# 612_jetracer_esp32s3_030006.net
KiCad netlist of a schematic drawn in EAGLE
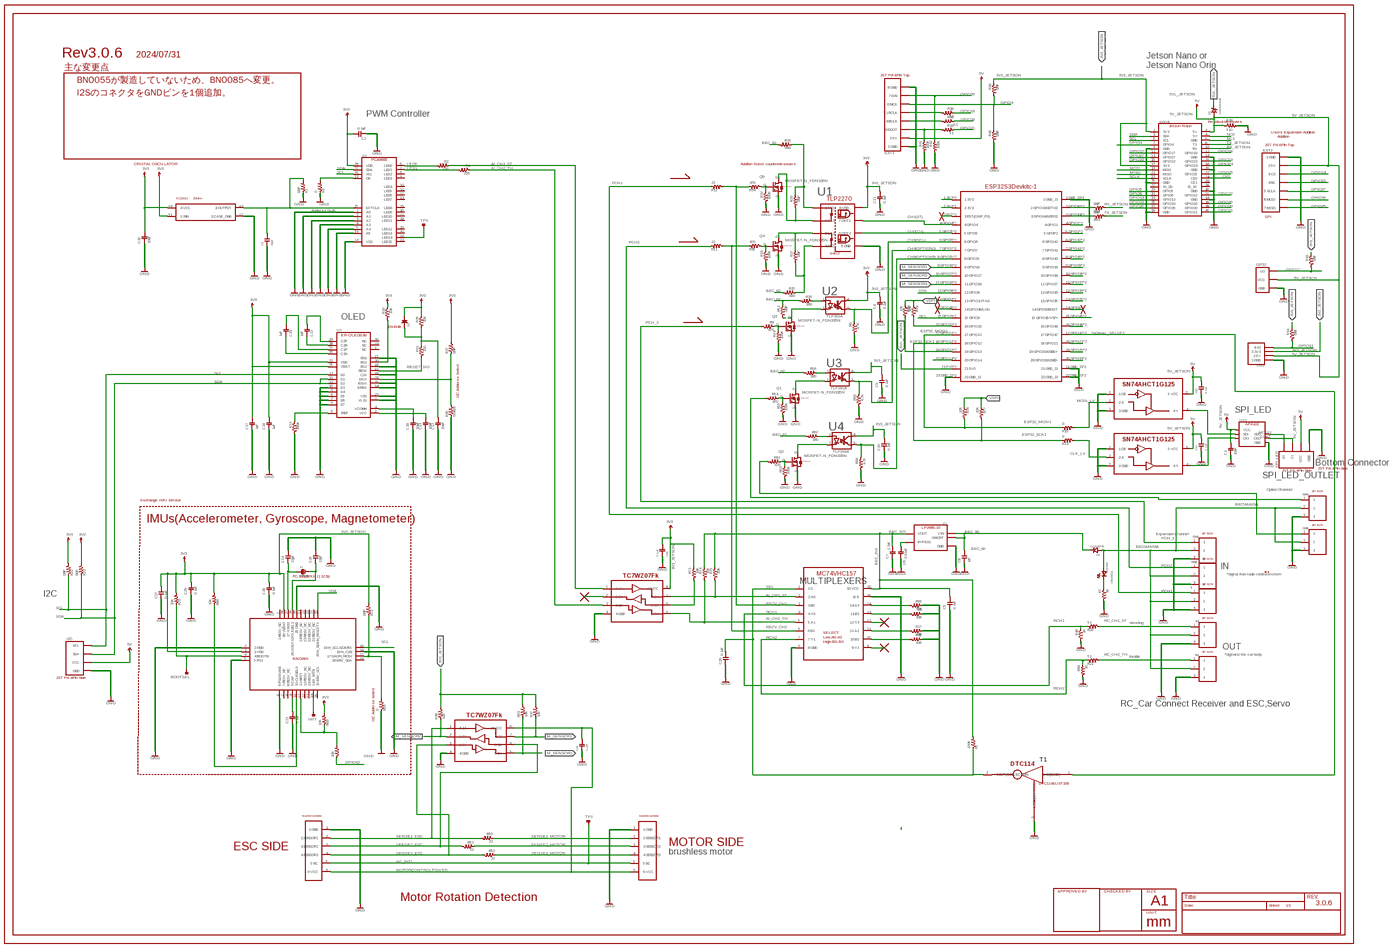
[diagram p0: schematic, sheet 1, overview]
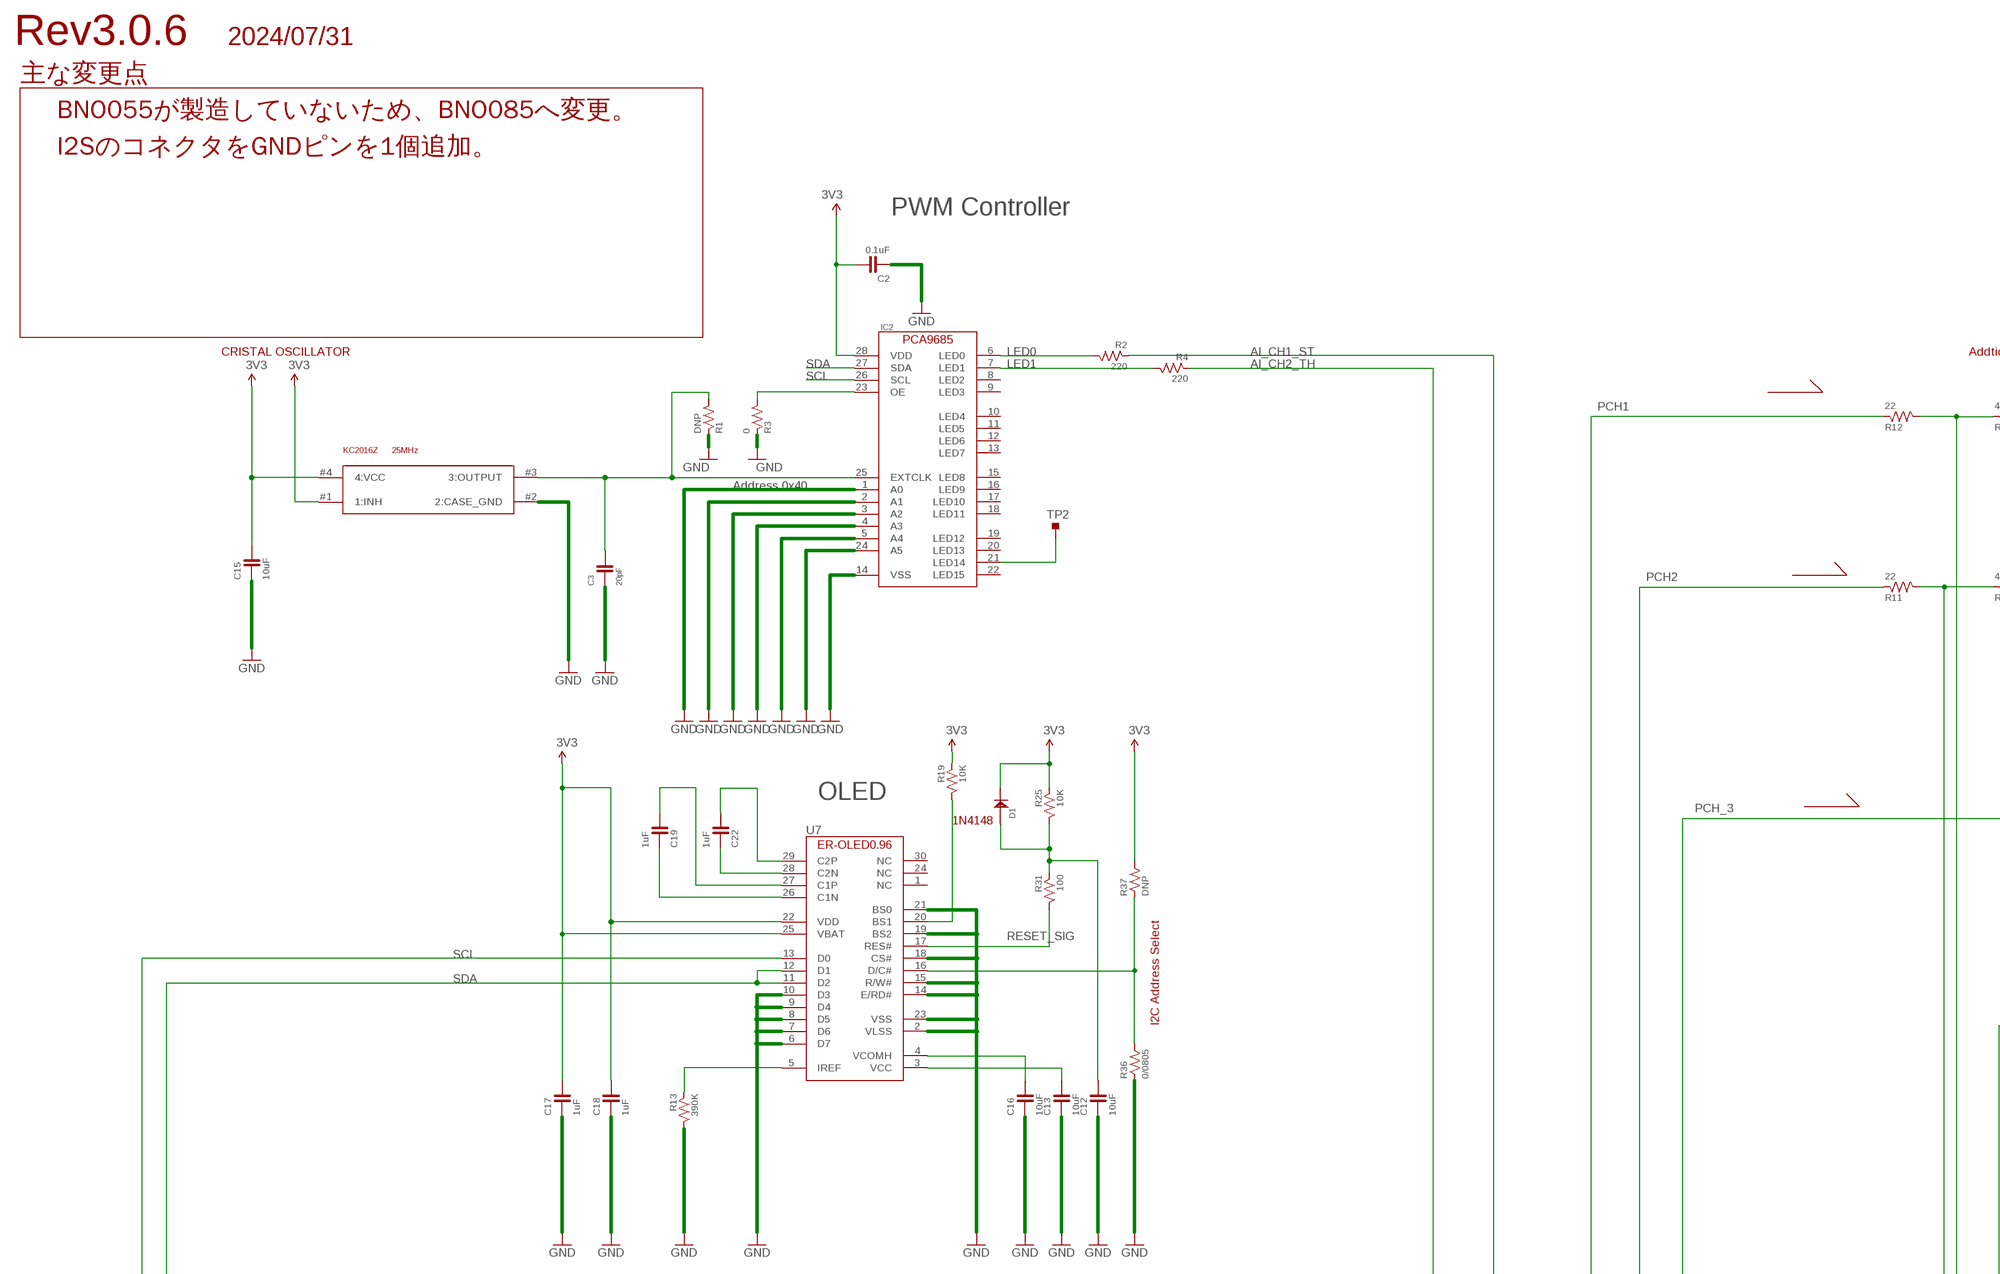
[diagram p1: schematic, sheet 1, part 1 of 4]
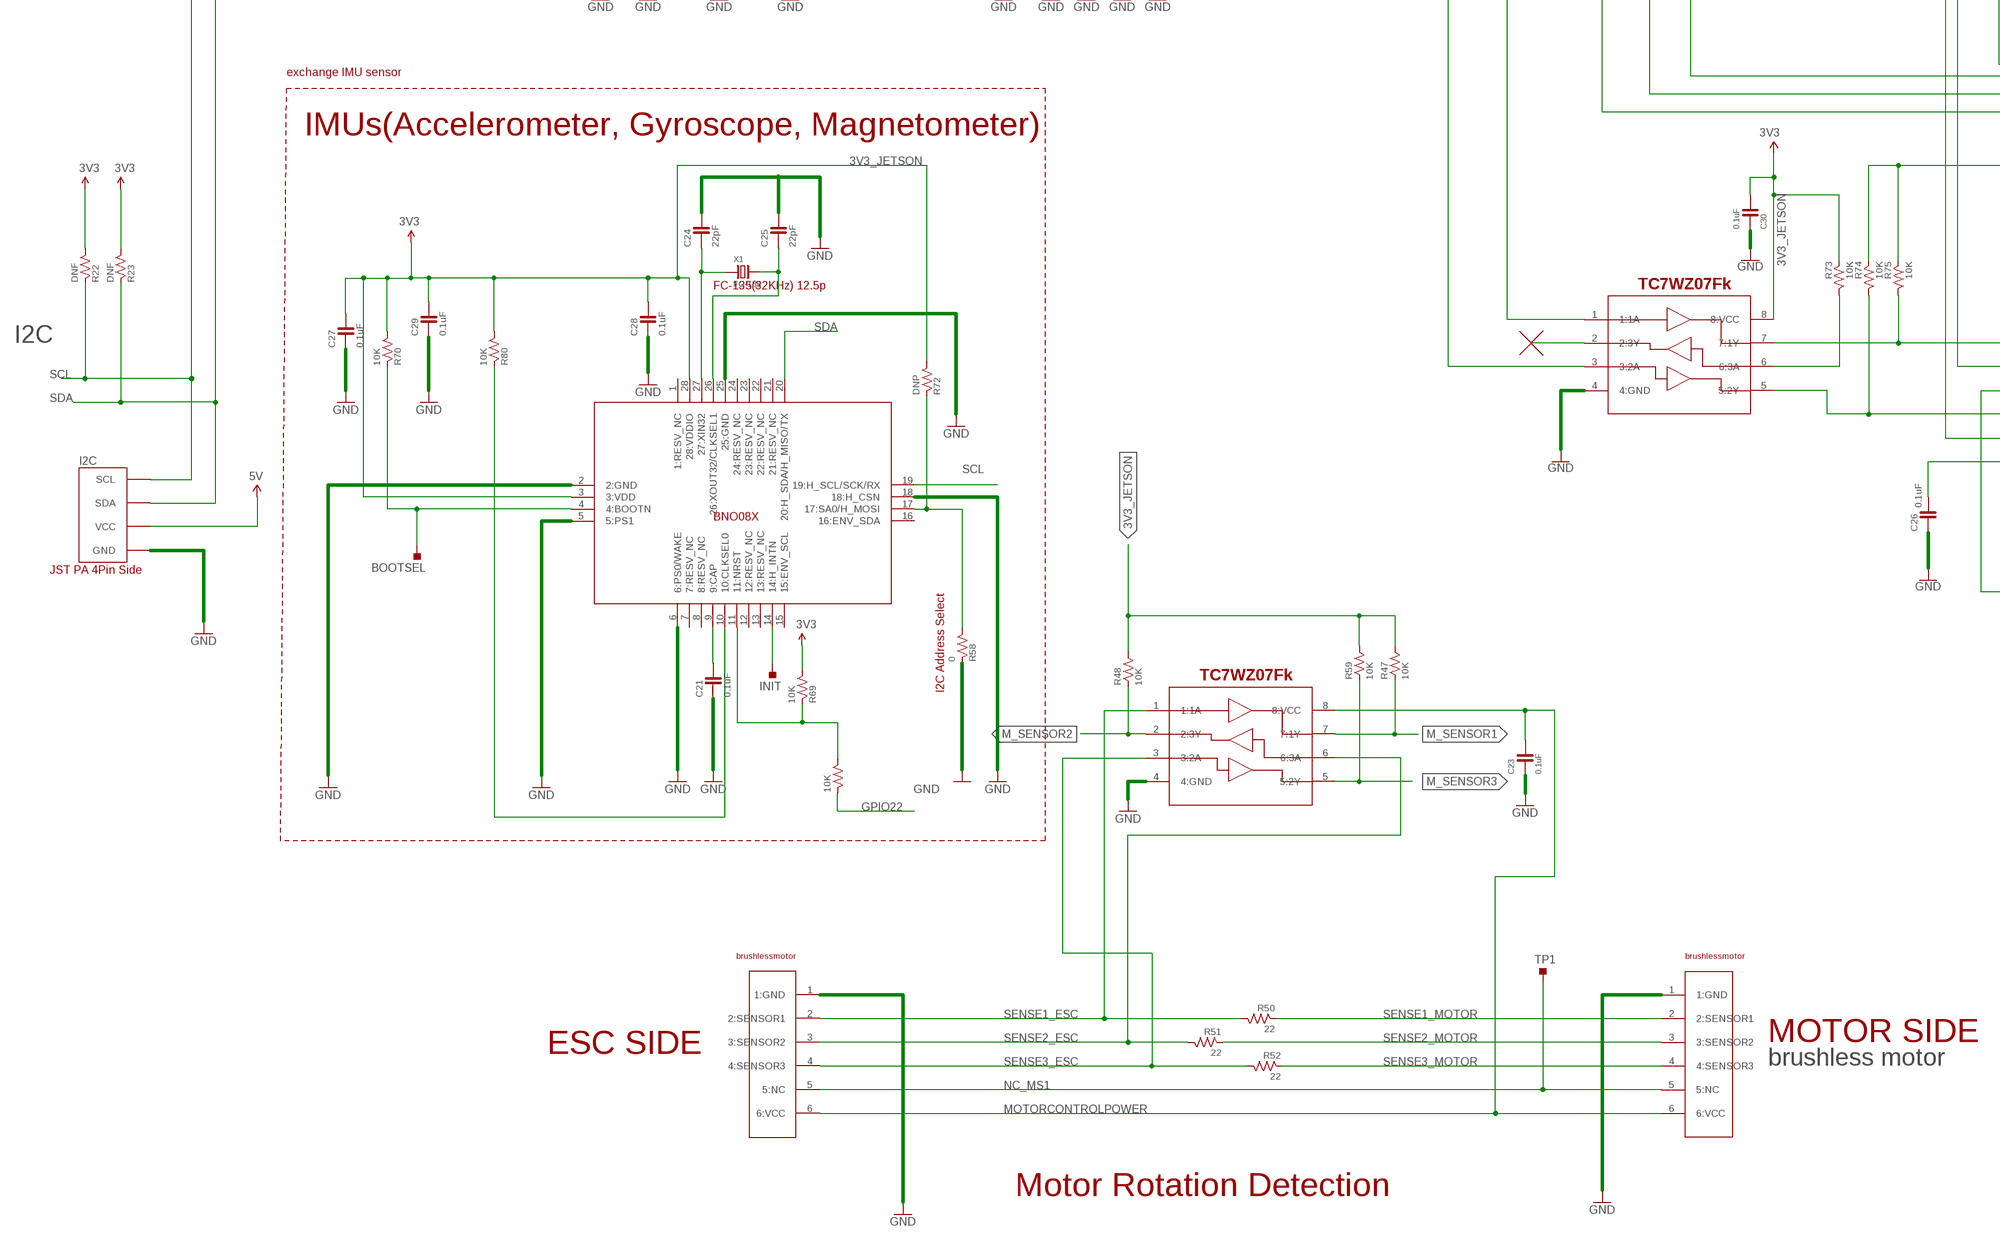
[diagram p2: schematic, sheet 1, part 2 of 4]
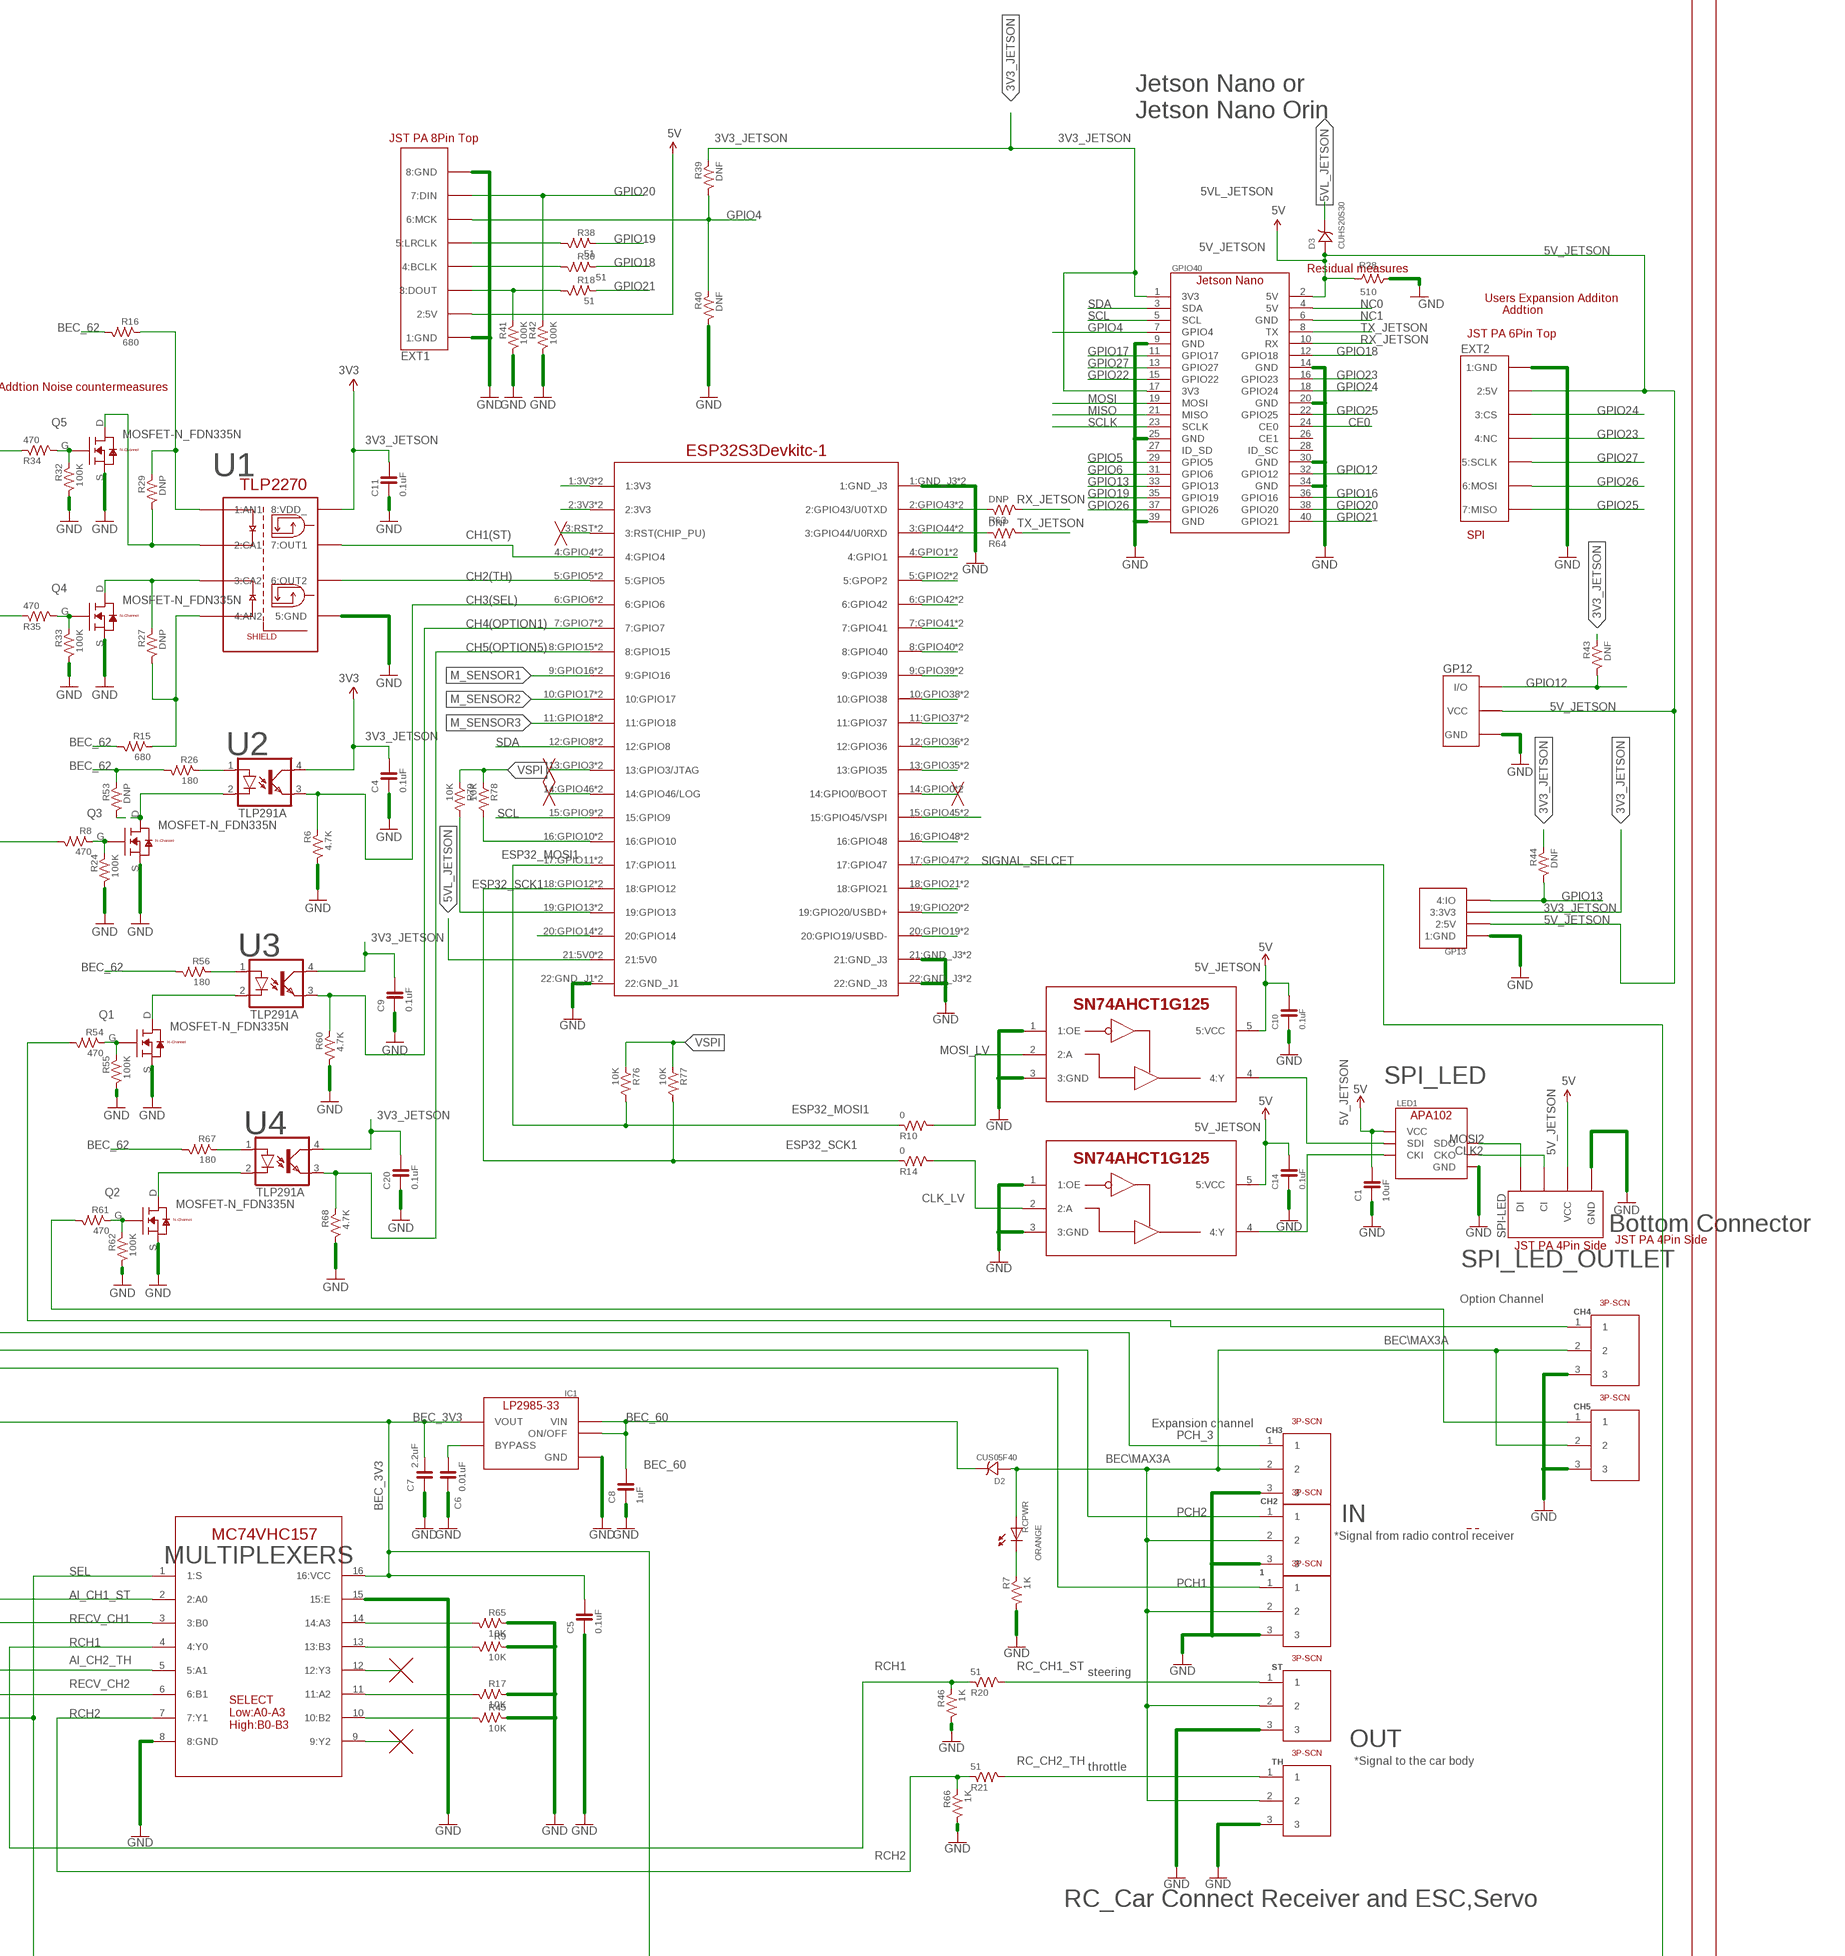
[diagram p3: schematic, sheet 1, part 3 of 4]
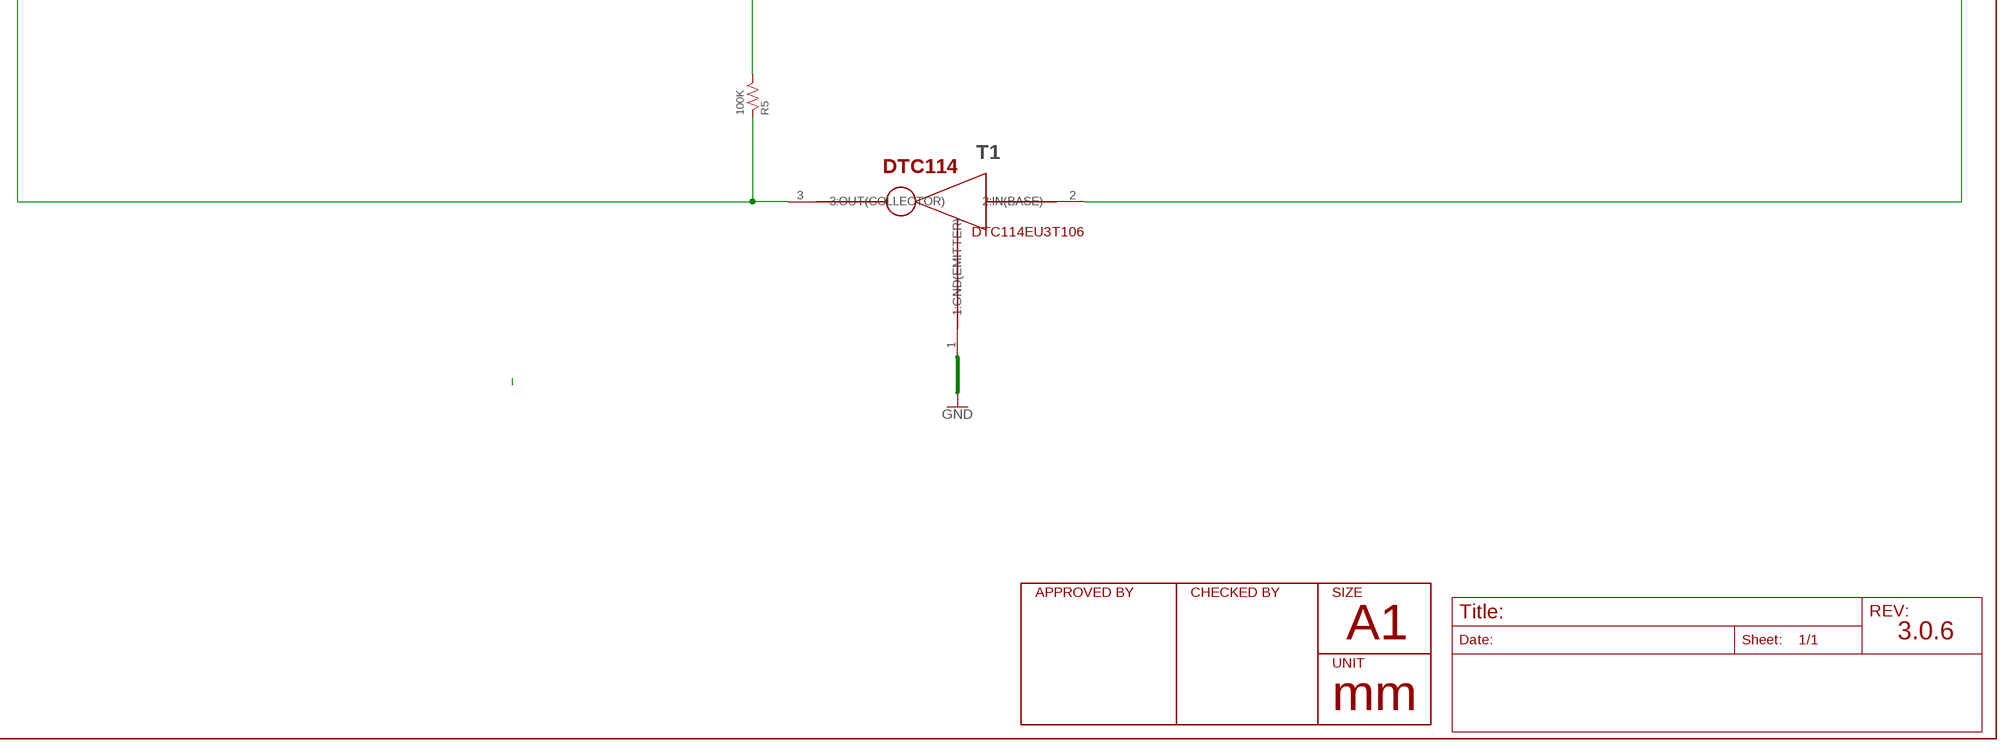
[diagram p4: schematic, sheet 1, part 4 of 4]

(export (version "E")
  (design (tool "Eeschema 10.0.6"))
  (components
    (comp (ref "1")
      (value "3P-SCN")
      (footprint "eagle-import:3P-SCN")
      (libsource (lib "eagle-import") (part "3P-SCN"))
    )
    (comp (ref "BOOTSEL")
      (value "TESTPOINT_TPS-SMD-10SN")
      (footprint "eagle-import:TESTPOINT_SMD-10SN")
      (libsource (lib "eagle-import") (part "TESTPOINT_TPS-SMD-10SN"))
    )
    (comp (ref "C1")
      (value "10uF")
      (footprint "eagle-import:0603")
      (libsource (lib "eagle-import") (part "CAPACITOR-0603"))
    )
    (comp (ref "C2")
      (value "0.1uF")
      (footprint "eagle-import:0603")
      (libsource (lib "eagle-import") (part "CAPACITOR-0603"))
    )
    (comp (ref "C3")
      (value "20pF")
      (footprint "eagle-import:0402")
      (libsource (lib "eagle-import") (part "CAPACITOR-0402"))
    )
    (comp (ref "C4")
      (value "0.1uF")
      (footprint "eagle-import:0603")
      (libsource (lib "eagle-import") (part "CAPACITOR-0603"))
    )
    (comp (ref "C5")
      (value "0.1uF")
      (footprint "eagle-import:0603")
      (fields (field (name "SPICEPREFIX") "C"))
      (libsource (lib "eagle-import") (part "CAPACITOR-0603"))
    )
    (comp (ref "C6")
      (value "0.01uF")
      (footprint "eagle-import:0603")
      (libsource (lib "eagle-import") (part "CAPACITOR-0603"))
    )
    (comp (ref "C7")
      (value "2.2uF")
      (footprint "eagle-import:0603")
      (libsource (lib "eagle-import") (part "CAPACITOR-0603"))
    )
    (comp (ref "C8")
      (value "1uF")
      (footprint "eagle-import:0603")
      (libsource (lib "eagle-import") (part "CAPACITOR-0603"))
    )
    (comp (ref "C9")
      (value "0.1uF")
      (footprint "eagle-import:0603")
      (libsource (lib "eagle-import") (part "CAPACITOR-0603"))
    )
    (comp (ref "C10")
      (value "0.1uF")
      (footprint "eagle-import:0402")
      (libsource (lib "eagle-import") (part "CAPACITOR-0402"))
    )
    (comp (ref "C11")
      (value "0.1uF")
      (footprint "eagle-import:0603")
      (libsource (lib "eagle-import") (part "CAPACITOR-0603"))
    )
    (comp (ref "C12")
      (value "10uF")
      (footprint "eagle-import:0603")
      (libsource (lib "eagle-import") (part "CAPACITOR-0603"))
    )
    (comp (ref "C13")
      (value "10uF")
      (footprint "eagle-import:0603")
      (libsource (lib "eagle-import") (part "CAPACITOR-0603"))
    )
    (comp (ref "C14")
      (value "0.1uF")
      (footprint "eagle-import:0402")
      (libsource (lib "eagle-import") (part "CAPACITOR-0402"))
    )
    (comp (ref "C15")
      (value "10uF")
      (footprint "eagle-import:0603")
      (libsource (lib "eagle-import") (part "CAPACITOR-0603"))
    )
    (comp (ref "C16")
      (value "10uF")
      (footprint "eagle-import:0603")
      (libsource (lib "eagle-import") (part "CAPACITOR-0603"))
    )
    (comp (ref "C17")
      (value "1uF")
      (footprint "eagle-import:0603")
      (libsource (lib "eagle-import") (part "CAPACITOR-0603"))
    )
    (comp (ref "C18")
      (value "1uF")
      (footprint "eagle-import:0603")
      (libsource (lib "eagle-import") (part "CAPACITOR-0603"))
    )
    (comp (ref "C19")
      (value "1uF")
      (footprint "eagle-import:0603")
      (libsource (lib "eagle-import") (part "CAPACITOR-0603"))
    )
    (comp (ref "C20")
      (value "0.1uF")
      (footprint "eagle-import:0603")
      (libsource (lib "eagle-import") (part "CAPACITOR-0603"))
    )
    (comp (ref "C21")
      (value "0.1uF")
      (footprint "eagle-import:0402")
      (libsource (lib "eagle-import") (part "CAPACITOR-0402"))
    )
    (comp (ref "C22")
      (value "1uF")
      (footprint "eagle-import:0603")
      (libsource (lib "eagle-import") (part "CAPACITOR-0603"))
    )
    (comp (ref "C23")
      (value "0.1uF")
      (footprint "eagle-import:0402")
      (libsource (lib "eagle-import") (part "CAPACITOR-0402"))
    )
    (comp (ref "C24")
      (value "22pF")
      (footprint "eagle-import:0402")
      (libsource (lib "eagle-import") (part "CAPACITOR-0402"))
    )
    (comp (ref "C25")
      (value "22pF")
      (footprint "eagle-import:0402")
      (libsource (lib "eagle-import") (part "CAPACITOR-0402"))
    )
    (comp (ref "C26")
      (value "0.1uF")
      (footprint "eagle-import:0603")
      (libsource (lib "eagle-import") (part "CAPACITOR-0603"))
    )
    (comp (ref "C27")
      (value "0.1uF")
      (footprint "eagle-import:0402")
      (libsource (lib "eagle-import") (part "CAPACITOR-0402"))
    )
    (comp (ref "C28")
      (value "0.1uF")
      (footprint "eagle-import:0402")
      (libsource (lib "eagle-import") (part "CAPACITOR-0402"))
    )
    (comp (ref "C29")
      (value "0.1uF")
      (footprint "eagle-import:0402")
      (libsource (lib "eagle-import") (part "CAPACITOR-0402"))
    )
    (comp (ref "C30")
      (value "0.1uF")
      (footprint "eagle-import:0402")
      (libsource (lib "eagle-import") (part "CAPACITOR-0402"))
    )
    (comp (ref "CH2")
      (value "3P-SCN")
      (footprint "eagle-import:3P-SCN")
      (libsource (lib "eagle-import") (part "3P-SCN"))
    )
    (comp (ref "CH3")
      (value "3P-SCN")
      (footprint "eagle-import:3P-SCN")
      (libsource (lib "eagle-import") (part "3P-SCN"))
    )
    (comp (ref "CH4")
      (value "3P-SCN")
      (footprint "eagle-import:3P-SCN")
      (libsource (lib "eagle-import") (part "3P-SCN"))
    )
    (comp (ref "CH5")
      (value "3P-SCN")
      (footprint "eagle-import:3P-SCN")
      (libsource (lib "eagle-import") (part "3P-SCN"))
    )
    (comp (ref "D1")
      (value "1N4148")
      (footprint "eagle-import:1N4148W")
      (libsource (lib "eagle-import") (part "1N4148"))
    )
    (comp (ref "D2")
      (value "CUS05F40")
      (footprint "eagle-import:CUS05F40")
      (libsource (lib "eagle-import") (part "CUS05F40"))
    )
    (comp (ref "D3")
      (value "CUHS20S30")
      (footprint "eagle-import:US2H")
      (libsource (lib "eagle-import") (part "CUHS20S30"))
    )
    (comp (ref "ESC_CON")
      (value "BRUSHLESSMOTOR_CON")
      (footprint "eagle-import:B6B-ZR")
      (libsource (lib "eagle-import") (part "BRUSHLESSMOTOR_CON"))
    )
    (comp (ref "EXT1")
      (value "FABO-I2S-2")
      (footprint "eagle-import:I2S-B08B-PASK-1")
      (libsource (lib "eagle-import") (part "FABO-I2S-2"))
    )
    (comp (ref "EXT2")
      (value "FABO-SPI-7PIN")
      (footprint "eagle-import:SPI-B07B-PASK-1")
      (libsource (lib "eagle-import") (part "FABO-SPI-7PIN"))
    )
    (comp (ref "GP12")
      (value "FABO_BRICK_3PIN-B03B-PASK-1")
      (footprint "eagle-import:FABO_BRICK_3PIN_B03B-PASK-1")
      (libsource (lib "eagle-import") (part "FABO_BRICK_3PIN-B03B-PASK-1"))
    )
    (comp (ref "GP13")
      (value "FABO-GPIO-2G")
      (footprint "eagle-import:GPIO-B04B-PASK-1")
      (libsource (lib "eagle-import") (part "FABO-GPIO-2G"))
    )
    (comp (ref "GPIO40")
      (value "JETSON_NANOJETSON_NANO_OVERALL")
      (footprint "eagle-import:JETSON_NANO_DEMENTION")
      (libsource (lib "eagle-import") (part "JETSON_NANOJETSON_NANO_OVERALL"))
    )
    (comp (ref "I2C")
      (value "FABO-I2C")
      (footprint "eagle-import:I2C-SM04B-PASS-1-FL")
      (libsource (lib "eagle-import") (part "FABO-I2C"))
    )
    (comp (ref "IC1")
      (value "LP2985-33DBVR")
      (footprint "eagle-import:SOT-23-5")
      (libsource (lib "eagle-import") (part "LP2985-33DBVR"))
    )
    (comp (ref "IC2")
      (value "PCA9685PW,BS")
      (footprint "eagle-import:PCA9685")
      (libsource (lib "eagle-import") (part "PCA9685PW,BS"))
    )
    (comp (ref "INIT")
      (value "TESTPOINT_TPS-SMD-10SN")
      (footprint "eagle-import:TESTPOINT_SMD-10SN")
      (libsource (lib "eagle-import") (part "TESTPOINT_TPS-SMD-10SN"))
    )
    (comp (ref "LED1")
      (value "APA102_IPIXEL")
      (footprint "eagle-import:APA102_2020")
      (libsource (lib "eagle-import") (part "APA102_IPIXEL"))
    )
    (comp (ref "MOTOR")
      (value "BRUSHLESSMOTOR_CON")
      (footprint "eagle-import:B6B-ZR")
      (libsource (lib "eagle-import") (part "BRUSHLESSMOTOR_CON"))
    )
    (comp (ref "Q1")
      (value "MOSFET-N_FDN335N")
      (footprint "eagle-import:SUPERSOT-3")
      (libsource (lib "eagle-import") (part "MOSFET-N_FDN335N"))
    )
    (comp (ref "Q2")
      (value "MOSFET-N_FDN335N")
      (footprint "eagle-import:SUPERSOT-3")
      (libsource (lib "eagle-import") (part "MOSFET-N_FDN335N"))
    )
    (comp (ref "Q3")
      (value "MOSFET-N_FDN335N")
      (footprint "eagle-import:SUPERSOT-3")
      (libsource (lib "eagle-import") (part "MOSFET-N_FDN335N"))
    )
    (comp (ref "Q4")
      (value "MOSFET-N_FDN335N")
      (footprint "eagle-import:SUPERSOT-3")
      (libsource (lib "eagle-import") (part "MOSFET-N_FDN335N"))
    )
    (comp (ref "Q5")
      (value "MOSFET-N_FDN335N")
      (footprint "eagle-import:SUPERSOT-3")
      (libsource (lib "eagle-import") (part "MOSFET-N_FDN335N"))
    )
    (comp (ref "R1")
      (value "DNP")
      (footprint "eagle-import:0603")
      (libsource (lib "eagle-import") (part "RESISTOR-0603"))
    )
    (comp (ref "R2")
      (value "220")
      (footprint "eagle-import:0402")
      (fields (field (name "SPICEPREFIX") "R"))
      (libsource (lib "eagle-import") (part "RESISTOR-0402"))
    )
    (comp (ref "R3")
      (value "0")
      (footprint "eagle-import:0603")
      (libsource (lib "eagle-import") (part "RESISTOR-0603"))
    )
    (comp (ref "R4")
      (value "220")
      (footprint "eagle-import:0402")
      (fields (field (name "SPICEPREFIX") "R"))
      (libsource (lib "eagle-import") (part "RESISTOR-0402"))
    )
    (comp (ref "R5")
      (value "100K")
      (footprint "eagle-import:0603")
      (libsource (lib "eagle-import") (part "RESISTOR-0603"))
    )
    (comp (ref "R6")
      (value "4.7K")
      (footprint "eagle-import:0603")
      (libsource (lib "eagle-import") (part "RESISTOR-0603"))
    )
    (comp (ref "R7")
      (value "1K")
      (footprint "eagle-import:0402")
      (fields (field (name "SPICEPREFIX") "R"))
      (libsource (lib "eagle-import") (part "RESISTOR-0402"))
    )
    (comp (ref "R8")
      (value "470")
      (footprint "eagle-import:0603")
      (libsource (lib "eagle-import") (part "RESISTOR-0603"))
    )
    (comp (ref "R9")
      (value "10K")
      (footprint "eagle-import:0402")
      (fields (field (name "SPICEPREFIX") "R"))
      (libsource (lib "eagle-import") (part "RESISTOR-0402"))
    )
    (comp (ref "R10")
      (value "0")
      (footprint "eagle-import:0603")
      (libsource (lib "eagle-import") (part "RESISTOR-0603"))
    )
    (comp (ref "R11")
      (value "22")
      (footprint "eagle-import:0603")
      (libsource (lib "eagle-import") (part "RESISTOR-0603"))
    )
    (comp (ref "R12")
      (value "22")
      (footprint "eagle-import:0603")
      (libsource (lib "eagle-import") (part "RESISTOR-0603"))
    )
    (comp (ref "R13")
      (value "390K")
      (footprint "eagle-import:0603")
      (libsource (lib "eagle-import") (part "RESISTOR-0603"))
    )
    (comp (ref "R14")
      (value "0")
      (footprint "eagle-import:0603")
      (libsource (lib "eagle-import") (part "RESISTOR-0603"))
    )
    (comp (ref "R15")
      (value "680")
      (footprint "eagle-import:0603")
      (libsource (lib "eagle-import") (part "RESISTOR-0603"))
    )
    (comp (ref "R16")
      (value "680")
      (footprint "eagle-import:0603")
      (libsource (lib "eagle-import") (part "RESISTOR-0603"))
    )
    (comp (ref "R17")
      (value "10K")
      (footprint "eagle-import:0402")
      (fields (field (name "SPICEPREFIX") "R"))
      (libsource (lib "eagle-import") (part "RESISTOR-0402"))
    )
    (comp (ref "R18")
      (value "51")
      (footprint "eagle-import:0603")
      (libsource (lib "eagle-import") (part "RESISTOR-0603"))
    )
    (comp (ref "R19")
      (value "10K")
      (footprint "eagle-import:0603")
      (libsource (lib "eagle-import") (part "RESISTOR-0603"))
    )
    (comp (ref "R20")
      (value "51")
      (footprint "eagle-import:0603")
      (libsource (lib "eagle-import") (part "RESISTOR-0603"))
    )
    (comp (ref "R21")
      (value "51")
      (footprint "eagle-import:0603")
      (libsource (lib "eagle-import") (part "RESISTOR-0603"))
    )
    (comp (ref "R22")
      (value "DNF")
      (footprint "eagle-import:0603")
      (libsource (lib "eagle-import") (part "RESISTOR-0603"))
    )
    (comp (ref "R23")
      (value "DNF")
      (footprint "eagle-import:0603")
      (libsource (lib "eagle-import") (part "RESISTOR-0603"))
    )
    (comp (ref "R24")
      (value "100K")
      (footprint "eagle-import:0603")
      (libsource (lib "eagle-import") (part "RESISTOR-0603"))
    )
    (comp (ref "R25")
      (value "10K")
      (footprint "eagle-import:0603")
      (libsource (lib "eagle-import") (part "RESISTOR-0603"))
    )
    (comp (ref "R26")
      (value "180")
      (footprint "eagle-import:0603")
      (libsource (lib "eagle-import") (part "RESISTOR-0603"))
    )
    (comp (ref "R27")
      (value "DNP")
      (footprint "eagle-import:0603")
      (libsource (lib "eagle-import") (part "RESISTOR-0603"))
    )
    (comp (ref "R28")
      (value "510")
      (footprint "eagle-import:0805")
      (libsource (lib "eagle-import") (part "RESISTOR-0805"))
    )
    (comp (ref "R29")
      (value "DNP")
      (footprint "eagle-import:0603")
      (libsource (lib "eagle-import") (part "RESISTOR-0603"))
    )
    (comp (ref "R30")
      (value "51")
      (footprint "eagle-import:0603")
      (libsource (lib "eagle-import") (part "RESISTOR-0603"))
    )
    (comp (ref "R31")
      (value "100")
      (footprint "eagle-import:0603")
      (libsource (lib "eagle-import") (part "RESISTOR-0603"))
    )
    (comp (ref "R32")
      (value "100K")
      (footprint "eagle-import:0603")
      (libsource (lib "eagle-import") (part "RESISTOR-0603"))
    )
    (comp (ref "R33")
      (value "100K")
      (footprint "eagle-import:0603")
      (libsource (lib "eagle-import") (part "RESISTOR-0603"))
    )
    (comp (ref "R34")
      (value "470")
      (footprint "eagle-import:0603")
      (libsource (lib "eagle-import") (part "RESISTOR-0603"))
    )
    (comp (ref "R35")
      (value "470")
      (footprint "eagle-import:0603")
      (libsource (lib "eagle-import") (part "RESISTOR-0603"))
    )
    (comp (ref "R36")
      (value "0/0805")
      (footprint "eagle-import:0805")
      (libsource (lib "eagle-import") (part "RESISTOR-0805"))
    )
    (comp (ref "R37")
      (value "DNP")
      (footprint "eagle-import:0805")
      (fields (field (name "SPICEPREFIX") "R"))
      (libsource (lib "eagle-import") (part "RESISTOR-0805"))
    )
    (comp (ref "R38")
      (value "51")
      (footprint "eagle-import:0603")
      (libsource (lib "eagle-import") (part "RESISTOR-0603"))
    )
    (comp (ref "R39")
      (value "DNF")
      (footprint "eagle-import:0603")
      (libsource (lib "eagle-import") (part "RESISTOR-0603"))
    )
    (comp (ref "R40")
      (value "DNF")
      (footprint "eagle-import:0603")
      (libsource (lib "eagle-import") (part "RESISTOR-0603"))
    )
    (comp (ref "R41")
      (value "100K")
      (footprint "eagle-import:0603")
      (libsource (lib "eagle-import") (part "RESISTOR-0603"))
    )
    (comp (ref "R42")
      (value "100K")
      (footprint "eagle-import:0603")
      (libsource (lib "eagle-import") (part "RESISTOR-0603"))
    )
    (comp (ref "R43")
      (value "DNF")
      (footprint "eagle-import:0603")
      (libsource (lib "eagle-import") (part "RESISTOR-0603"))
    )
    (comp (ref "R44")
      (value "DNF")
      (footprint "eagle-import:0603")
      (libsource (lib "eagle-import") (part "RESISTOR-0603"))
    )
    (comp (ref "R45")
      (value "10K")
      (footprint "eagle-import:0402")
      (fields (field (name "SPICEPREFIX") "R"))
      (libsource (lib "eagle-import") (part "RESISTOR-0402"))
    )
    (comp (ref "R46")
      (value "1K")
      (footprint "eagle-import:0402")
      (fields (field (name "SPICEPREFIX") "R"))
      (libsource (lib "eagle-import") (part "RESISTOR-0402"))
    )
    (comp (ref "R47")
      (value "10K")
      (footprint "eagle-import:0402")
      (libsource (lib "eagle-import") (part "RESISTOR-0402"))
    )
    (comp (ref "R48")
      (value "10K")
      (footprint "eagle-import:0402")
      (libsource (lib "eagle-import") (part "RESISTOR-0402"))
    )
    (comp (ref "R50")
      (value "22")
      (footprint "eagle-import:0603")
      (libsource (lib "eagle-import") (part "RESISTOR-0603"))
    )
    (comp (ref "R51")
      (value "22")
      (footprint "eagle-import:0603")
      (libsource (lib "eagle-import") (part "RESISTOR-0603"))
    )
    (comp (ref "R52")
      (value "22")
      (footprint "eagle-import:0603")
      (libsource (lib "eagle-import") (part "RESISTOR-0603"))
    )
    (comp (ref "R53")
      (value "DNP")
      (footprint "eagle-import:0603")
      (libsource (lib "eagle-import") (part "RESISTOR-0603"))
    )
    (comp (ref "R54")
      (value "470")
      (footprint "eagle-import:0603")
      (libsource (lib "eagle-import") (part "RESISTOR-0603"))
    )
    (comp (ref "R55")
      (value "100K")
      (footprint "eagle-import:0603")
      (libsource (lib "eagle-import") (part "RESISTOR-0603"))
    )
    (comp (ref "R56")
      (value "180")
      (footprint "eagle-import:0603")
      (libsource (lib "eagle-import") (part "RESISTOR-0603"))
    )
    (comp (ref "R58")
      (value "0")
      (footprint "eagle-import:0402")
      (libsource (lib "eagle-import") (part "RESISTOR-0402"))
    )
    (comp (ref "R59")
      (value "10K")
      (footprint "eagle-import:0402")
      (libsource (lib "eagle-import") (part "RESISTOR-0402"))
    )
    (comp (ref "R60")
      (value "4.7K")
      (footprint "eagle-import:0603")
      (libsource (lib "eagle-import") (part "RESISTOR-0603"))
    )
    (comp (ref "R61")
      (value "470")
      (footprint "eagle-import:0603")
      (libsource (lib "eagle-import") (part "RESISTOR-0603"))
    )
    (comp (ref "R62")
      (value "100K")
      (footprint "eagle-import:0603")
      (libsource (lib "eagle-import") (part "RESISTOR-0603"))
    )
    (comp (ref "R63")
      (value "DNP")
      (footprint "eagle-import:0603")
      (libsource (lib "eagle-import") (part "RESISTOR-0603"))
    )
    (comp (ref "R64")
      (value "DNP")
      (footprint "eagle-import:0603")
      (libsource (lib "eagle-import") (part "RESISTOR-0603"))
    )
    (comp (ref "R65")
      (value "10K")
      (footprint "eagle-import:0402")
      (fields (field (name "SPICEPREFIX") "R"))
      (libsource (lib "eagle-import") (part "RESISTOR-0402"))
    )
    (comp (ref "R66")
      (value "1K")
      (footprint "eagle-import:0402")
      (fields (field (name "SPICEPREFIX") "R"))
      (libsource (lib "eagle-import") (part "RESISTOR-0402"))
    )
    (comp (ref "R67")
      (value "180")
      (footprint "eagle-import:0603")
      (libsource (lib "eagle-import") (part "RESISTOR-0603"))
    )
    (comp (ref "R68")
      (value "4.7K")
      (footprint "eagle-import:0603")
      (libsource (lib "eagle-import") (part "RESISTOR-0603"))
    )
    (comp (ref "R69")
      (value "10K")
      (footprint "eagle-import:0402")
      (libsource (lib "eagle-import") (part "RESISTOR-0402"))
    )
    (comp (ref "R70")
      (value "10K")
      (footprint "eagle-import:0402")
      (libsource (lib "eagle-import") (part "RESISTOR-0402"))
    )
    (comp (ref "R71")
      (value "10K")
      (footprint "eagle-import:0402")
      (libsource (lib "eagle-import") (part "RESISTOR-0402"))
    )
    (comp (ref "R72")
      (value "DNP")
      (footprint "eagle-import:0402")
      (fields (field (name "SPICEPREFIX") "R"))
      (libsource (lib "eagle-import") (part "RESISTOR-0402"))
    )
    (comp (ref "R73")
      (value "10K")
      (footprint "eagle-import:0402")
      (fields (field (name "SPICEPREFIX") "R"))
      (libsource (lib "eagle-import") (part "RESISTOR-0402"))
    )
    (comp (ref "R74")
      (value "10K")
      (footprint "eagle-import:0402")
      (fields (field (name "SPICEPREFIX") "R"))
      (libsource (lib "eagle-import") (part "RESISTOR-0402"))
    )
    (comp (ref "R75")
      (value "10K")
      (footprint "eagle-import:0402")
      (fields (field (name "SPICEPREFIX") "R"))
      (libsource (lib "eagle-import") (part "RESISTOR-0402"))
    )
    (comp (ref "R76")
      (value "10K")
      (footprint "eagle-import:0402")
      (fields (field (name "SPICEPREFIX") "R"))
      (libsource (lib "eagle-import") (part "RESISTOR-0402"))
    )
    (comp (ref "R77")
      (value "10K")
      (footprint "eagle-import:0402")
      (fields (field (name "SPICEPREFIX") "R"))
      (libsource (lib "eagle-import") (part "RESISTOR-0402"))
    )
    (comp (ref "R78")
      (value "10K")
      (footprint "eagle-import:0402")
      (fields (field (name "SPICEPREFIX") "R"))
      (libsource (lib "eagle-import") (part "RESISTOR-0402"))
    )
    (comp (ref "R79")
      (value "10K")
      (footprint "eagle-import:0402")
      (fields (field (name "SPICEPREFIX") "R"))
      (libsource (lib "eagle-import") (part "RESISTOR-0402"))
    )
    (comp (ref "R80")
      (value "10K")
      (footprint "eagle-import:0402")
      (libsource (lib "eagle-import") (part "RESISTOR-0402"))
    )
    (comp (ref "RCPWR")
      (value "ORANGE")
      (footprint "eagle-import:0603")
      (libsource (lib "eagle-import") (part "LED-0603"))
    )
    (comp (ref "SPI-LED")
      (value "FABO-SPI-LED")
      (footprint "eagle-import:SPI-SM04B-PASS-1-FL")
      (libsource (lib "eagle-import") (part "FABO-SPI-LED"))
    )
    (comp (ref "ST")
      (value "3P-SCN")
      (footprint "eagle-import:3P-SCN")
      (libsource (lib "eagle-import") (part "3P-SCN"))
    )
    (comp (ref "T1")
      (value "DTC114EU3")
      (footprint "eagle-import:SOT-323FL_SC-85(UMT3F)")
      (libsource (lib "eagle-import") (part "DTC114EU3"))
    )
    (comp (ref "TH")
      (value "3P-SCN")
      (footprint "eagle-import:3P-SCN")
      (libsource (lib "eagle-import") (part "3P-SCN"))
    )
    (comp (ref "TP1")
      (value "TESTPOINT_TPS-SMD-10SN")
      (footprint "eagle-import:TESTPOINT_SMD-10SN")
      (libsource (lib "eagle-import") (part "TESTPOINT_TPS-SMD-10SN"))
    )
    (comp (ref "TP2")
      (value "TESTPOINT_TPS-SMD-10SN")
      (footprint "eagle-import:TESTPOINT_SMD-10SN")
      (libsource (lib "eagle-import") (part "TESTPOINT_TPS-SMD-10SN"))
    )
    (comp (ref "U$1")
      (value "MC74VHC157")
      (footprint "eagle-import:MC74VHC157_TSSOP-16")
      (libsource (lib "eagle-import") (part "MC74VHC157"))
    )
    (comp (ref "U$3")
      (value "TC7WZ07FK")
      (footprint "eagle-import:SOT-765")
      (libsource (lib "eagle-import") (part "TC7WZ07FK"))
    )
    (comp (ref "U$5")
      (value "TC7WZ07FK")
      (footprint "eagle-import:SOT-765")
      (libsource (lib "eagle-import") (part "TC7WZ07FK"))
    )
    (comp (ref "U$9")
      (value "SN74AHCT1G125")
      (footprint "eagle-import:SOT-1DOT1")
      (libsource (lib "eagle-import") (part "SN74AHCT1G125"))
    )
    (comp (ref "U$10")
      (value "SN74AHCT1G125")
      (footprint "eagle-import:SOT-1DOT1")
      (libsource (lib "eagle-import") (part "SN74AHCT1G125"))
    )
    (comp (ref "U$11")
      (value "KC2016Z")
      (footprint "eagle-import:KC2016Z")
      (libsource (lib "eagle-import") (part "KC2016Z"))
    )
    (comp (ref "U$14")
      (value "ESP32S3DEVKITC-1-DUAL")
      (footprint "eagle-import:ESP32S3DEVKITC-1-DUAL")
      (libsource (lib "eagle-import") (part "ESP32S3DEVKITC-1-DUAL"))
    )
    (comp (ref "U1")
      (value "TLP2270")
      (footprint "eagle-import:TLP2270")
      (libsource (lib "eagle-import") (part "TLP2270"))
    )
    (comp (ref "U2")
      (value "TLP291A")
      (footprint "eagle-import:11-3C1")
      (libsource (lib "eagle-import") (part "TLP291A"))
    )
    (comp (ref "U3")
      (value "TLP291A")
      (footprint "eagle-import:11-3C1")
      (libsource (lib "eagle-import") (part "TLP291A"))
    )
    (comp (ref "U4")
      (value "TLP291A")
      (footprint "eagle-import:11-3C1")
      (libsource (lib "eagle-import") (part "TLP291A"))
    )
    (comp (ref "U6")
      (value "BNO085")
      (footprint "eagle-import:BNO08X(LGA)")
      (libsource (lib "eagle-import") (part "BNO085"))
    )
    (comp (ref "U7")
      (value "ER-OLED0.96-1ER-CON30HT-1")
      (footprint "eagle-import:ER-CON30HT-1")
      (libsource (lib "eagle-import") (part "ER-OLED0.96-1ER-CON30HT-1"))
    )
    (comp (ref "X1")
      (value "FC-135")
      (footprint "eagle-import:FC-135")
      (libsource (lib "eagle-import") (part "FC-135"))
    )
  )
  (nets
    (net (code "1") (name "/AI_CH1_ST") (class "Default")
      (node (ref "R2") (pin "1") (pinfunction "1_1") (pintype "bidirectional"))
      (node (ref "U$5") (pin "1") (pinfunction "1:1A_1") (pintype "input"))
    )
    (net (code "2") (name "/AI_CH2_TH") (class "Default")
      (node (ref "R4") (pin "1") (pinfunction "1_1") (pintype "bidirectional"))
      (node (ref "U$5") (pin "3") (pinfunction "3:2A_3") (pintype "input"))
    )
    (net (code "3") (name "/BEC\\MAX3A") (class "Default")
      (node (ref "1") (pin "2") (pinfunction "2_2") (pintype "power_in"))
      (node (ref "CH2") (pin "2") (pinfunction "2_2") (pintype "power_in"))
      (node (ref "CH3") (pin "2") (pinfunction "2_2") (pintype "power_in"))
      (node (ref "CH4") (pin "2") (pinfunction "2_2") (pintype "power_in"))
      (node (ref "CH5") (pin "2") (pinfunction "2_2") (pintype "power_in"))
      (node (ref "D2") (pin "A") (pinfunction "ANODE_A") (pintype "bidirectional"))
      (node (ref "RCPWR") (pin "ANODE") (pinfunction "ANODE_ANODE") (pintype "passive"))
      (node (ref "ST") (pin "2") (pinfunction "2_2") (pintype "power_in"))
      (node (ref "TH") (pin "2") (pinfunction "2_2") (pintype "power_in"))
    )
    (net (code "4") (name "/BEC_3V3") (class "Default")
      (node (ref "C5") (pin "2") (pinfunction "2_2") (pintype "passive"))
      (node (ref "C7") (pin "2") (pinfunction "2_2") (pintype "passive"))
      (node (ref "IC1") (pin "5") (pinfunction "VOUT_5") (pintype "output"))
      (node (ref "R5") (pin "2") (pinfunction "2_2") (pintype "bidirectional"))
      (node (ref "R74") (pin "1") (pinfunction "1_1") (pintype "bidirectional"))
      (node (ref "R75") (pin "1") (pinfunction "1_1") (pintype "bidirectional"))
      (node (ref "U$1") (pin "16") (pinfunction "16:VCC_16") (pintype "bidirectional"))
    )
    (net (code "5") (name "/BEC_60") (class "Default")
      (node (ref "C8") (pin "2") (pinfunction "2_2") (pintype "passive"))
      (node (ref "D2") (pin "C") (pinfunction "CATHODE_C") (pintype "bidirectional"))
      (node (ref "IC1") (pin "1") (pinfunction "VIN_1") (pintype "input"))
      (node (ref "IC1") (pin "3") (pinfunction "ON/OFF_3") (pintype "input"))
    )
    (net (code "6") (name "/BEC_62") (class "Default")
      (node (ref "R15") (pin "2") (pinfunction "2_2") (pintype "bidirectional"))
      (node (ref "R16") (pin "2") (pinfunction "2_2") (pintype "bidirectional"))
      (node (ref "R26") (pin "2") (pinfunction "2_2") (pintype "bidirectional"))
      (node (ref "R53") (pin "1") (pinfunction "1_1") (pintype "bidirectional"))
      (node (ref "R56") (pin "2") (pinfunction "2_2") (pintype "bidirectional"))
      (node (ref "R67") (pin "2") (pinfunction "2_2") (pintype "bidirectional"))
    )
    (net (code "7") (name "/CE0") (class "Default")
      (node (ref "GPIO40") (pin "24") (pinfunction "CE0_24") (pintype "bidirectional"))
    )
    (net (code "8") (name "/CH1(ST)") (class "Default")
      (node (ref "U$14") (pin "4:GPIO4") (pinfunction "4:GPIO4_4:GPIO4") (pintype "bidirectional"))
      (node (ref "U$14") (pin "4:GPIO4_L") (pinfunction "4:GPIO4_4:GPIO4_L") (pintype "bidirectional"))
      (node (ref "U1") (pin "7") (pinfunction "7:OUT1_7") (pintype "bidirectional"))
    )
    (net (code "9") (name "/CH2(TH)") (class "Default")
      (node (ref "U$14") (pin "5:GPIO5") (pinfunction "5:GPIO5_5:GPIO5") (pintype "bidirectional"))
      (node (ref "U$14") (pin "5:GPIO5_L") (pinfunction "5:GPIO5_5:GPIO5_L") (pintype "bidirectional"))
      (node (ref "U1") (pin "6") (pinfunction "6:OUT2_6") (pintype "bidirectional"))
    )
    (net (code "10") (name "/CH3(SEL)") (class "Default")
      (node (ref "R6") (pin "1") (pinfunction "1_1") (pintype "bidirectional"))
      (node (ref "U$14") (pin "6:GPIO6") (pinfunction "6:GPIO6_6:GPIO6") (pintype "bidirectional"))
      (node (ref "U$14") (pin "6:GPIO6_L") (pinfunction "6:GPIO6_6:GPIO6_L") (pintype "bidirectional"))
      (node (ref "U2") (pin "3") (pinfunction "EMI_3") (pintype "passive"))
    )
    (net (code "11") (name "/CH4(OPTION1)") (class "Default")
      (node (ref "R60") (pin "1") (pinfunction "1_1") (pintype "bidirectional"))
      (node (ref "U$14") (pin "7:GPIO7") (pinfunction "7:GPIO7_7:GPIO7") (pintype "bidirectional"))
      (node (ref "U$14") (pin "7:GPIO7_L") (pinfunction "7:GPIO7_7:GPIO7_L") (pintype "bidirectional"))
      (node (ref "U3") (pin "3") (pinfunction "EMI_3") (pintype "passive"))
    )
    (net (code "12") (name "/CH5(OPTION5)") (class "Default")
      (node (ref "R68") (pin "1") (pinfunction "1_1") (pintype "bidirectional"))
      (node (ref "U$14") (pin "8:GPIO15") (pinfunction "8:GPIO15_8:GPIO15") (pintype "bidirectional"))
      (node (ref "U$14") (pin "8:GPIO15_L") (pinfunction "8:GPIO15_8:GPIO15_L") (pintype "bidirectional"))
      (node (ref "U4") (pin "3") (pinfunction "EMI_3") (pintype "passive"))
    )
    (net (code "13") (name "/CLK2") (class "Default")
      (node (ref "LED1") (pin "CKO") (pinfunction "CKO_CKO") (pintype "bidirectional"))
      (node (ref "SPI-LED") (pin "CI") (pinfunction "CI_CI") (pintype "bidirectional"))
    )
    (net (code "14") (name "/CLK_LV") (class "Default")
      (node (ref "R14") (pin "2") (pinfunction "2_2") (pintype "bidirectional"))
      (node (ref "U$10") (pin "2") (pinfunction "2:A_2") (pintype "input"))
    )
    (net (code "15") (name "/ESP32_MOSI1") (class "Default")
      (node (ref "R10") (pin "1") (pinfunction "1_1") (pintype "bidirectional"))
      (node (ref "R76") (pin "2") (pinfunction "2_2") (pintype "bidirectional"))
      (node (ref "U$14") (pin "17:GPIO11") (pinfunction "17:GPIO11_17:GPIO11") (pintype "bidirectional"))
      (node (ref "U$14") (pin "17:GPIO11_L") (pinfunction "17:GPIO11_17:GPIO11_L") (pintype "bidirectional"))
    )
    (net (code "16") (name "/ESP32_SCK1") (class "Default")
      (node (ref "R14") (pin "1") (pinfunction "1_1") (pintype "bidirectional"))
      (node (ref "R77") (pin "2") (pinfunction "2_2") (pintype "bidirectional"))
      (node (ref "U$14") (pin "18:GPIO12") (pinfunction "18:GPIO12_18:GPIO12") (pintype "bidirectional"))
      (node (ref "U$14") (pin "18:GPIO12_L") (pinfunction "18:GPIO12_18:GPIO12_L") (pintype "bidirectional"))
    )
    (net (code "17") (name "/GPIO4") (class "Default")
      (node (ref "EXT1") (pin "6:MCK") (pinfunction "6:MCK_6:MCK") (pintype "output"))
      (node (ref "GPIO40") (pin "7") (pinfunction "GPIO4_7") (pintype "bidirectional"))
      (node (ref "R39") (pin "2") (pinfunction "2_2") (pintype "bidirectional"))
      (node (ref "R40") (pin "1") (pinfunction "1_1") (pintype "bidirectional"))
    )
    (net (code "18") (name "/GPIO5") (class "Default")
      (node (ref "GPIO40") (pin "29") (pinfunction "GPIO5_29") (pintype "bidirectional"))
    )
    (net (code "19") (name "/GPIO6") (class "Default")
      (node (ref "GPIO40") (pin "31") (pinfunction "GPIO6_31") (pintype "bidirectional"))
    )
    (net (code "20") (name "/GPIO12") (class "Default")
      (node (ref "GP12") (pin "I/O") (pinfunction "I/O_I/O") (pintype "bidirectional"))
      (node (ref "GPIO40") (pin "32") (pinfunction "GPIO12_32") (pintype "bidirectional"))
      (node (ref "R43") (pin "2") (pinfunction "2_2") (pintype "bidirectional"))
    )
    (net (code "21") (name "/GPIO13") (class "Default")
      (node (ref "GP13") (pin "IO") (pinfunction "4:IO_IO") (pintype "bidirectional"))
      (node (ref "GPIO40") (pin "33") (pinfunction "GPIO13_33") (pintype "bidirectional"))
      (node (ref "R44") (pin "2") (pinfunction "2_2") (pintype "bidirectional"))
    )
    (net (code "22") (name "/GPIO16") (class "Default")
      (node (ref "GPIO40") (pin "36") (pinfunction "GPIO16_36") (pintype "bidirectional"))
    )
    (net (code "23") (name "/GPIO17") (class "Default")
      (node (ref "GPIO40") (pin "11") (pinfunction "GPIO17_11") (pintype "bidirectional"))
    )
    (net (code "24") (name "/GPIO18") (class "Default")
      (node (ref "GPIO40") (pin "12") (pinfunction "GPIO18_12") (pintype "bidirectional"))
      (node (ref "R30") (pin "1") (pinfunction "1_1") (pintype "bidirectional"))
    )
    (net (code "25") (name "/GPIO19") (class "Default")
      (node (ref "GPIO40") (pin "35") (pinfunction "GPIO19_35") (pintype "bidirectional"))
      (node (ref "R38") (pin "1") (pinfunction "1_1") (pintype "bidirectional"))
    )
    (net (code "26") (name "/GPIO20") (class "Default")
      (node (ref "EXT1") (pin "7:DIN") (pinfunction "7:DIN_7:DIN") (pintype "output"))
      (node (ref "GPIO40") (pin "38") (pinfunction "GPIO20_38") (pintype "bidirectional"))
      (node (ref "R42") (pin "1") (pinfunction "1_1") (pintype "bidirectional"))
    )
    (net (code "27") (name "/GPIO21") (class "Default")
      (node (ref "GPIO40") (pin "40") (pinfunction "GPIO21_40") (pintype "bidirectional"))
      (node (ref "R18") (pin "1") (pinfunction "1_1") (pintype "bidirectional"))
    )
    (net (code "28") (name "/GPIO22") (class "Default")
      (node (ref "GPIO40") (pin "15") (pinfunction "GPIO22_15") (pintype "bidirectional"))
      (node (ref "R71") (pin "1") (pinfunction "1_1") (pintype "bidirectional"))
    )
    (net (code "29") (name "/GPIO23") (class "Default")
      (node (ref "EXT2") (pin "4") (pinfunction "4:NC_4") (pintype "bidirectional"))
      (node (ref "GPIO40") (pin "16") (pinfunction "GPIO23_16") (pintype "bidirectional"))
    )
    (net (code "30") (name "/GPIO24") (class "Default")
      (node (ref "EXT2") (pin "3") (pinfunction "3:CS_3") (pintype "bidirectional"))
      (node (ref "GPIO40") (pin "18") (pinfunction "GPIO24_18") (pintype "bidirectional"))
    )
    (net (code "31") (name "/GPIO25") (class "Default")
      (node (ref "EXT2") (pin "7") (pinfunction "7:MISO_7") (pintype "bidirectional"))
      (node (ref "GPIO40") (pin "22") (pinfunction "GPIO25_22") (pintype "bidirectional"))
    )
    (net (code "32") (name "/GPIO26") (class "Default")
      (node (ref "EXT2") (pin "6") (pinfunction "6:MOSI_6") (pintype "bidirectional"))
      (node (ref "GPIO40") (pin "37") (pinfunction "GPIO26_37") (pintype "bidirectional"))
    )
    (net (code "33") (name "/GPIO27") (class "Default")
      (node (ref "EXT2") (pin "5") (pinfunction "5:SCLK_5") (pintype "bidirectional"))
      (node (ref "GPIO40") (pin "13") (pinfunction "GPIO27_13") (pintype "bidirectional"))
    )
    (net (code "34") (name "/LED0") (class "Default")
      (node (ref "IC2") (pin "6") (pinfunction "LED0_6") (pintype "bidirectional"))
      (node (ref "R2") (pin "2") (pinfunction "2_2") (pintype "bidirectional"))
    )
    (net (code "35") (name "/LED1") (class "Default")
      (node (ref "IC2") (pin "7") (pinfunction "LED1_7") (pintype "bidirectional"))
      (node (ref "R4") (pin "2") (pinfunction "2_2") (pintype "bidirectional"))
    )
    (net (code "36") (name "/MISO") (class "Default")
      (node (ref "GPIO40") (pin "21") (pinfunction "MISO_21") (pintype "bidirectional"))
    )
    (net (code "37") (name "/MOSI") (class "Default")
      (node (ref "GPIO40") (pin "19") (pinfunction "MOSI_19") (pintype "bidirectional"))
    )
    (net (code "38") (name "/MOSI2") (class "Default")
      (node (ref "LED1") (pin "SDO") (pinfunction "SDO_SDO") (pintype "bidirectional"))
      (node (ref "SPI-LED") (pin "DI") (pinfunction "DI_DI") (pintype "bidirectional"))
    )
    (net (code "39") (name "/MOSI_LV") (class "Default")
      (node (ref "R10") (pin "2") (pinfunction "2_2") (pintype "bidirectional"))
      (node (ref "U$9") (pin "2") (pinfunction "2:A_2") (pintype "input"))
    )
    (net (code "40") (name "/MOTORCONTROLPOWER") (class "Default")
      (node (ref "C23") (pin "2") (pinfunction "2_2") (pintype "passive"))
      (node (ref "ESC_CON") (pin "6") (pinfunction "6:VCC_6") (pintype "bidirectional"))
      (node (ref "MOTOR") (pin "6") (pinfunction "6:VCC_6") (pintype "bidirectional"))
      (node (ref "U$3") (pin "8") (pinfunction "8:VCC_8") (pintype "power_in"))
    )
    (net (code "41") (name "/NC0") (class "Default")
      (node (ref "GPIO40") (pin "4") (pinfunction "5V_4") (pintype "bidirectional"))
    )
    (net (code "42") (name "/NC1") (class "Default")
      (node (ref "GPIO40") (pin "6") (pinfunction "GND_6") (pintype "bidirectional"))
    )
    (net (code "43") (name "/NC_MS1") (class "Default")
      (node (ref "ESC_CON") (pin "5") (pinfunction "5:NC_5") (pintype "bidirectional"))
      (node (ref "MOTOR") (pin "5") (pinfunction "5:NC_5") (pintype "bidirectional"))
      (node (ref "TP1") (pin "TP") (pinfunction "TP_TP") (pintype "passive"))
    )
    (net (code "44") (name "/PCH1") (class "Default")
      (node (ref "1") (pin "1") (pinfunction "1_1") (pintype "bidirectional"))
      (node (ref "R12") (pin "1") (pinfunction "1_1") (pintype "bidirectional"))
    )
    (net (code "45") (name "/PCH2") (class "Default")
      (node (ref "CH2") (pin "1") (pinfunction "1_1") (pintype "bidirectional"))
      (node (ref "R11") (pin "1") (pinfunction "1_1") (pintype "bidirectional"))
    )
    (net (code "46") (name "/PCH_3") (class "Default")
      (node (ref "CH3") (pin "1") (pinfunction "1_1") (pintype "bidirectional"))
      (node (ref "R8") (pin "2") (pinfunction "2_2") (pintype "bidirectional"))
    )
    (net (code "47") (name "/RCH1") (class "Default")
      (node (ref "R20") (pin "1") (pinfunction "1_1") (pintype "bidirectional"))
      (node (ref "R46") (pin "1") (pinfunction "1_1") (pintype "bidirectional"))
      (node (ref "U$1") (pin "4") (pinfunction "4:Y0_4") (pintype "bidirectional"))
    )
    (net (code "48") (name "/RCH2") (class "Default")
      (node (ref "R21") (pin "1") (pinfunction "1_1") (pintype "bidirectional"))
      (node (ref "R66") (pin "1") (pinfunction "1_1") (pintype "bidirectional"))
      (node (ref "U$1") (pin "7") (pinfunction "7:Y1_7") (pintype "bidirectional"))
    )
    (net (code "49") (name "/RC_CH1_ST") (class "Default")
      (node (ref "R20") (pin "2") (pinfunction "2_2") (pintype "bidirectional"))
      (node (ref "ST") (pin "1") (pinfunction "1_1") (pintype "bidirectional"))
    )
    (net (code "50") (name "/RC_CH2_TH") (class "Default")
      (node (ref "R21") (pin "2") (pinfunction "2_2") (pintype "bidirectional"))
      (node (ref "TH") (pin "1") (pinfunction "1_1") (pintype "bidirectional"))
    )
    (net (code "51") (name "/RECV_CH1") (class "Default")
      (node (ref "R12") (pin "2") (pinfunction "2_2") (pintype "bidirectional"))
      (node (ref "R34") (pin "1") (pinfunction "1_1") (pintype "bidirectional"))
      (node (ref "U$1") (pin "3") (pinfunction "3:B0_3") (pintype "bidirectional"))
    )
    (net (code "52") (name "/RECV_CH2") (class "Default")
      (node (ref "R11") (pin "2") (pinfunction "2_2") (pintype "bidirectional"))
      (node (ref "R35") (pin "1") (pinfunction "1_1") (pintype "bidirectional"))
      (node (ref "U$1") (pin "6") (pinfunction "6:B1_6") (pintype "bidirectional"))
    )
    (net (code "53") (name "/RESET_SIG") (class "Default")
      (node (ref "R31") (pin "2") (pinfunction "2_2") (pintype "bidirectional"))
      (node (ref "U7") (pin "17") (pinfunction "RES#_17") (pintype "bidirectional"))
    )
    (net (code "54") (name "/RX_JETSON") (class "Default")
      (node (ref "GPIO40") (pin "10") (pinfunction "RX_10") (pintype "bidirectional"))
      (node (ref "R63") (pin "2") (pinfunction "2_2") (pintype "bidirectional"))
    )
    (net (code "55") (name "/SCL") (class "Default")
      (node (ref "GPIO40") (pin "5") (pinfunction "SCL_5") (pintype "bidirectional"))
      (node (ref "I2C") (pin "SCL") (pinfunction "SCL_SCL") (pintype "bidirectional"))
      (node (ref "IC2") (pin "26") (pinfunction "SCL_26") (pintype "bidirectional"))
      (node (ref "R22") (pin "1") (pinfunction "1_1") (pintype "bidirectional"))
      (node (ref "U$14") (pin "15:GPIO9") (pinfunction "15:GPIO9_15:GPIO9") (pintype "bidirectional"))
      (node (ref "U$14") (pin "15:GPIO9_L") (pinfunction "15:GPIO9_15:GPIO9_L") (pintype "bidirectional"))
      (node (ref "U6") (pin "19") (pinfunction "19:H_SCL/SCK/RX_19") (pintype "bidirectional"))
      (node (ref "U7") (pin "13") (pinfunction "D0_13") (pintype "bidirectional"))
    )
    (net (code "56") (name "/SCLK") (class "Default")
      (node (ref "GPIO40") (pin "23") (pinfunction "SCLK_23") (pintype "bidirectional"))
    )
    (net (code "57") (name "/SDA") (class "Default")
      (node (ref "GPIO40") (pin "3") (pinfunction "SDA_3") (pintype "bidirectional"))
      (node (ref "I2C") (pin "SDA") (pinfunction "SDA_SDA") (pintype "bidirectional"))
      (node (ref "IC2") (pin "27") (pinfunction "SDA_27") (pintype "bidirectional"))
      (node (ref "R23") (pin "1") (pinfunction "1_1") (pintype "bidirectional"))
      (node (ref "U$14") (pin "12:GPIO8") (pinfunction "12:GPIO8_12:GPIO8") (pintype "bidirectional"))
      (node (ref "U$14") (pin "12:GPIO8_L") (pinfunction "12:GPIO8_12:GPIO8_L") (pintype "bidirectional"))
      (node (ref "U6") (pin "20") (pinfunction "20:H_SDA/H_MISO/TX_20") (pintype "bidirectional"))
      (node (ref "U7") (pin "11") (pinfunction "D2_11") (pintype "bidirectional"))
      (node (ref "U7") (pin "12") (pinfunction "D1_12") (pintype "bidirectional"))
    )
    (net (code "58") (name "/SEL") (class "Default")
      (node (ref "C26") (pin "2") (pinfunction "2_2") (pintype "passive"))
      (node (ref "R5") (pin "1") (pinfunction "1_1") (pintype "bidirectional"))
      (node (ref "T1") (pin "3") (pinfunction "3:OUT(COLLECTOR)_3") (pintype "output"))
      (node (ref "U$1") (pin "1") (pinfunction "1:S_1") (pintype "bidirectional"))
    )
    (net (code "59") (name "/SENSE1_ESC") (class "Default")
      (node (ref "ESC_CON") (pin "2") (pinfunction "2:SENSOR1_2") (pintype "bidirectional"))
      (node (ref "R50") (pin "2") (pinfunction "2_2") (pintype "bidirectional"))
      (node (ref "U$3") (pin "1") (pinfunction "1:1A_1") (pintype "input"))
    )
    (net (code "60") (name "/SENSE1_MOTOR") (class "Default")
      (node (ref "MOTOR") (pin "2") (pinfunction "2:SENSOR1_2") (pintype "bidirectional"))
      (node (ref "R50") (pin "1") (pinfunction "1_1") (pintype "bidirectional"))
    )
    (net (code "61") (name "/SENSE2_ESC") (class "Default")
      (node (ref "ESC_CON") (pin "3") (pinfunction "3:SENSOR2_3") (pintype "bidirectional"))
      (node (ref "R51") (pin "2") (pinfunction "2_2") (pintype "bidirectional"))
      (node (ref "U$3") (pin "6") (pinfunction "6:3A_6") (pintype "input"))
    )
    (net (code "62") (name "/SENSE2_MOTOR") (class "Default")
      (node (ref "MOTOR") (pin "3") (pinfunction "3:SENSOR2_3") (pintype "bidirectional"))
      (node (ref "R51") (pin "1") (pinfunction "1_1") (pintype "bidirectional"))
    )
    (net (code "63") (name "/SENSE3_ESC") (class "Default")
      (node (ref "ESC_CON") (pin "4") (pinfunction "4:SENSOR3_4") (pintype "bidirectional"))
      (node (ref "R52") (pin "2") (pinfunction "2_2") (pintype "bidirectional"))
      (node (ref "U$3") (pin "3") (pinfunction "3:2A_3") (pintype "input"))
    )
    (net (code "64") (name "/SENSE3_MOTOR") (class "Default")
      (node (ref "MOTOR") (pin "4") (pinfunction "4:SENSOR3_4") (pintype "bidirectional"))
      (node (ref "R52") (pin "1") (pinfunction "1_1") (pintype "bidirectional"))
    )
    (net (code "65") (name "/SIGNAL_SELCET") (class "Default")
      (node (ref "T1") (pin "2") (pinfunction "2:IN(BASE)_2") (pintype "input"))
      (node (ref "U$14") (pin "17:GPIO47") (pinfunction "17:GPIO47_17:GPIO47") (pintype "bidirectional"))
      (node (ref "U$14") (pin "17:GPIO47_R") (pinfunction "17:GPIO47_17:GPIO47_R") (pintype "bidirectional"))
    )
    (net (code "66") (name "/TX_JETSON") (class "Default")
      (node (ref "GPIO40") (pin "8") (pinfunction "TX_8") (pintype "bidirectional"))
      (node (ref "R64") (pin "2") (pinfunction "2_2") (pintype "bidirectional"))
    )
    (net (code "67") (name "3V3_JETSON") (class "Default")
      (node (ref "C11") (pin "2") (pinfunction "2_2") (pintype "passive"))
      (node (ref "C15") (pin "2") (pinfunction "2_2") (pintype "passive"))
      (node (ref "C17") (pin "2") (pinfunction "2_2") (pintype "passive"))
      (node (ref "C18") (pin "2") (pinfunction "2_2") (pintype "passive"))
      (node (ref "C2") (pin "2") (pinfunction "2_2") (pintype "passive"))
      (node (ref "C20") (pin "2") (pinfunction "2_2") (pintype "passive"))
      (node (ref "C27") (pin "2") (pinfunction "2_2") (pintype "passive"))
      (node (ref "C28") (pin "2") (pinfunction "2_2") (pintype "passive"))
      (node (ref "C29") (pin "2") (pinfunction "2_2") (pintype "passive"))
      (node (ref "C30") (pin "2") (pinfunction "2_2") (pintype "passive"))
      (node (ref "C4") (pin "2") (pinfunction "2_2") (pintype "passive"))
      (node (ref "C9") (pin "2") (pinfunction "2_2") (pintype "passive"))
      (node (ref "D1") (pin "CATHODE") (pinfunction "CATHODE_CATHODE") (pintype "bidirectional"))
      (node (ref "GP13") (pin "3V3") (pinfunction "3:3V3_3V3") (pintype "bidirectional"))
      (node (ref "GPIO40") (pin "1") (pinfunction "3V3_1") (pintype "bidirectional"))
      (node (ref "GPIO40") (pin "17") (pinfunction "3V3_17") (pintype "bidirectional"))
      (node (ref "IC2") (pin "28") (pinfunction "VDD_28") (pintype "bidirectional"))
      (node (ref "R19") (pin "1") (pinfunction "1_1") (pintype "bidirectional"))
      (node (ref "R22") (pin "2") (pinfunction "2_2") (pintype "bidirectional"))
      (node (ref "R23") (pin "2") (pinfunction "2_2") (pintype "bidirectional"))
      (node (ref "R25") (pin "1") (pinfunction "1_1") (pintype "bidirectional"))
      (node (ref "R37") (pin "2") (pinfunction "2_2") (pintype "bidirectional"))
      (node (ref "R39") (pin "1") (pinfunction "1_1") (pintype "bidirectional"))
      (node (ref "R43") (pin "1") (pinfunction "1_1") (pintype "bidirectional"))
      (node (ref "R44") (pin "1") (pinfunction "1_1") (pintype "bidirectional"))
      (node (ref "R47") (pin "2") (pinfunction "2_2") (pintype "bidirectional"))
      (node (ref "R48") (pin "2") (pinfunction "2_2") (pintype "bidirectional"))
      (node (ref "R59") (pin "2") (pinfunction "2_2") (pintype "bidirectional"))
      (node (ref "R69") (pin "2") (pinfunction "2_2") (pintype "bidirectional"))
      (node (ref "R70") (pin "2") (pinfunction "2_2") (pintype "bidirectional"))
      (node (ref "R72") (pin "2") (pinfunction "2_2") (pintype "bidirectional"))
      (node (ref "R73") (pin "1") (pinfunction "1_1") (pintype "bidirectional"))
      (node (ref "R80") (pin "2") (pinfunction "2_2") (pintype "bidirectional"))
      (node (ref "U$11") (pin "#1") (pinfunction "1:INH_#1") (pintype "bidirectional"))
      (node (ref "U$11") (pin "#4") (pinfunction "4:VCC_#4") (pintype "bidirectional"))
      (node (ref "U$5") (pin "8") (pinfunction "8:VCC_8") (pintype "power_in"))
      (node (ref "U1") (pin "8") (pinfunction "8:VDD__8") (pintype "bidirectional"))
      (node (ref "U2") (pin "4") (pinfunction "COL_4") (pintype "passive"))
      (node (ref "U3") (pin "4") (pinfunction "COL_4") (pintype "passive"))
      (node (ref "U4") (pin "4") (pinfunction "COL_4") (pintype "passive"))
      (node (ref "U6") (pin "28") (pinfunction "28:VDDIO_28") (pintype "power_in"))
      (node (ref "U6") (pin "3") (pinfunction "3:VDD_3") (pintype "power_in"))
      (node (ref "U7") (pin "22") (pinfunction "VDD_22") (pintype "bidirectional"))
      (node (ref "U7") (pin "25") (pinfunction "VBAT_25") (pintype "bidirectional"))
    )
    (net (code "68") (name "5V") (class "Default")
      (node (ref "C1") (pin "2") (pinfunction "2_2") (pintype "passive"))
      (node (ref "C10") (pin "2") (pinfunction "2_2") (pintype "passive"))
      (node (ref "C14") (pin "2") (pinfunction "2_2") (pintype "passive"))
      (node (ref "D3") (pin "A") (pinfunction "ANODE_A") (pintype "passive"))
      (node (ref "EXT1") (pin "2:5V") (pinfunction "2:5V_2:5V") (pintype "power_in"))
      (node (ref "EXT2") (pin "2") (pinfunction "2:5V_2") (pintype "bidirectional"))
      (node (ref "GP12") (pin "VCC") (pinfunction "VCC_VCC") (pintype "bidirectional"))
      (node (ref "GP13") (pin "5V") (pinfunction "2:5V_5V") (pintype "bidirectional"))
      (node (ref "GPIO40") (pin "2") (pinfunction "5V_2") (pintype "bidirectional"))
      (node (ref "I2C") (pin "5V") (pinfunction "VCC_5V") (pintype "bidirectional"))
      (node (ref "LED1") (pin "VCC") (pinfunction "VCC_VCC") (pintype "bidirectional"))
      (node (ref "R28") (pin "2") (pinfunction "2_2") (pintype "bidirectional"))
      (node (ref "SPI-LED") (pin "5V") (pinfunction "VCC_5V") (pintype "bidirectional"))
      (node (ref "U$10") (pin "5") (pinfunction "5:VCC_5") (pintype "power_in"))
      (node (ref "U$9") (pin "5") (pinfunction "5:VCC_5") (pintype "power_in"))
    )
    (net (code "69") (name "5VL_JETSON") (class "Default")
      (node (ref "D3") (pin "K") (pinfunction "CATHODE_K") (pintype "passive"))
      (node (ref "U$14") (pin "21:5V0") (pinfunction "21:5V0_21:5V0") (pintype "power_in"))
      (node (ref "U$14") (pin "21:5V0_L") (pinfunction "21:5V0_21:5V0_L") (pintype "power_in"))
    )
    (net (code "70") (name "GND") (class "Default")
      (node (ref "1") (pin "3") (pinfunction "3_3") (pintype "power_in"))
      (node (ref "C1") (pin "1") (pinfunction "1_1") (pintype "passive"))
      (node (ref "C10") (pin "1") (pinfunction "1_1") (pintype "passive"))
      (node (ref "C11") (pin "1") (pinfunction "1_1") (pintype "passive"))
      (node (ref "C12") (pin "1") (pinfunction "1_1") (pintype "passive"))
      (node (ref "C13") (pin "1") (pinfunction "1_1") (pintype "passive"))
      (node (ref "C14") (pin "1") (pinfunction "1_1") (pintype "passive"))
      (node (ref "C15") (pin "1") (pinfunction "1_1") (pintype "passive"))
      (node (ref "C16") (pin "1") (pinfunction "1_1") (pintype "passive"))
      (node (ref "C17") (pin "1") (pinfunction "1_1") (pintype "passive"))
      (node (ref "C18") (pin "1") (pinfunction "1_1") (pintype "passive"))
      (node (ref "C2") (pin "1") (pinfunction "1_1") (pintype "passive"))
      (node (ref "C20") (pin "1") (pinfunction "1_1") (pintype "passive"))
      (node (ref "C21") (pin "1") (pinfunction "1_1") (pintype "passive"))
      (node (ref "C23") (pin "1") (pinfunction "1_1") (pintype "passive"))
      (node (ref "C24") (pin "2") (pinfunction "2_2") (pintype "passive"))
      (node (ref "C25") (pin "2") (pinfunction "2_2") (pintype "passive"))
      (node (ref "C26") (pin "1") (pinfunction "1_1") (pintype "passive"))
      (node (ref "C27") (pin "1") (pinfunction "1_1") (pintype "passive"))
      (node (ref "C28") (pin "1") (pinfunction "1_1") (pintype "passive"))
      (node (ref "C29") (pin "1") (pinfunction "1_1") (pintype "passive"))
      (node (ref "C3") (pin "1") (pinfunction "1_1") (pintype "passive"))
      (node (ref "C30") (pin "1") (pinfunction "1_1") (pintype "passive"))
      (node (ref "C4") (pin "1") (pinfunction "1_1") (pintype "passive"))
      (node (ref "C5") (pin "1") (pinfunction "1_1") (pintype "passive"))
      (node (ref "C6") (pin "1") (pinfunction "1_1") (pintype "passive"))
      (node (ref "C7") (pin "1") (pinfunction "1_1") (pintype "passive"))
      (node (ref "C8") (pin "1") (pinfunction "1_1") (pintype "passive"))
      (node (ref "C9") (pin "1") (pinfunction "1_1") (pintype "passive"))
      (node (ref "CH2") (pin "3") (pinfunction "3_3") (pintype "power_in"))
      (node (ref "CH3") (pin "3") (pinfunction "3_3") (pintype "power_in"))
      (node (ref "CH4") (pin "3") (pinfunction "3_3") (pintype "power_in"))
      (node (ref "CH5") (pin "3") (pinfunction "3_3") (pintype "power_in"))
      (node (ref "ESC_CON") (pin "1") (pinfunction "1:GND_1") (pintype "bidirectional"))
      (node (ref "EXT1") (pin "1:GND") (pinfunction "1:GND_1:GND") (pintype "power_in"))
      (node (ref "EXT1") (pin "8:GND") (pinfunction "8:GND_8:GND") (pintype "power_in"))
      (node (ref "EXT2") (pin "1") (pinfunction "1:GND_1") (pintype "bidirectional"))
      (node (ref "GP12") (pin "GND") (pinfunction "GND_GND") (pintype "bidirectional"))
      (node (ref "GP13") (pin "GND") (pinfunction "1:GND_GND") (pintype "bidirectional"))
      (node (ref "GPIO40") (pin "14") (pinfunction "GND_14") (pintype "bidirectional"))
      (node (ref "GPIO40") (pin "20") (pinfunction "GND_20") (pintype "bidirectional"))
      (node (ref "GPIO40") (pin "25") (pinfunction "GND_25") (pintype "bidirectional"))
      (node (ref "GPIO40") (pin "30") (pinfunction "GND_30") (pintype "bidirectional"))
      (node (ref "GPIO40") (pin "34") (pinfunction "GND_34") (pintype "bidirectional"))
      (node (ref "GPIO40") (pin "39") (pinfunction "GND_39") (pintype "bidirectional"))
      (node (ref "GPIO40") (pin "9") (pinfunction "GND_9") (pintype "bidirectional"))
      (node (ref "I2C") (pin "GND") (pinfunction "GND_GND") (pintype "bidirectional"))
      (node (ref "IC1") (pin "2") (pinfunction "GND_2") (pintype "power_in"))
      (node (ref "IC2") (pin "1") (pinfunction "A0_1") (pintype "bidirectional"))
      (node (ref "IC2") (pin "14") (pinfunction "VSS_14") (pintype "bidirectional"))
      (node (ref "IC2") (pin "2") (pinfunction "A1_2") (pintype "bidirectional"))
      (node (ref "IC2") (pin "24") (pinfunction "A5_24") (pintype "bidirectional"))
      (node (ref "IC2") (pin "3") (pinfunction "A2_3") (pintype "bidirectional"))
      (node (ref "IC2") (pin "4") (pinfunction "A3_4") (pintype "bidirectional"))
      (node (ref "IC2") (pin "5") (pinfunction "A4_5") (pintype "bidirectional"))
      (node (ref "LED1") (pin "GND") (pinfunction "GND_GND") (pintype "bidirectional"))
      (node (ref "MOTOR") (pin "1") (pinfunction "1:GND_1") (pintype "bidirectional"))
      (node (ref "Q1") (pin "S") (pinfunction "S_S") (pintype "passive"))
      (node (ref "Q2") (pin "S") (pinfunction "S_S") (pintype "passive"))
      (node (ref "Q3") (pin "S") (pinfunction "S_S") (pintype "passive"))
      (node (ref "Q4") (pin "S") (pinfunction "S_S") (pintype "passive"))
      (node (ref "Q5") (pin "S") (pinfunction "S_S") (pintype "passive"))
      (node (ref "R1") (pin "1") (pinfunction "1_1") (pintype "bidirectional"))
      (node (ref "R13") (pin "2") (pinfunction "2_2") (pintype "bidirectional"))
      (node (ref "R17") (pin "1") (pinfunction "1_1") (pintype "bidirectional"))
      (node (ref "R24") (pin "2") (pinfunction "2_2") (pintype "bidirectional"))
      (node (ref "R28") (pin "1") (pinfunction "1_1") (pintype "bidirectional"))
      (node (ref "R3") (pin "1") (pinfunction "1_1") (pintype "bidirectional"))
      (node (ref "R32") (pin "2") (pinfunction "2_2") (pintype "bidirectional"))
      (node (ref "R33") (pin "2") (pinfunction "2_2") (pintype "bidirectional"))
      (node (ref "R36") (pin "1") (pinfunction "1_1") (pintype "bidirectional"))
      (node (ref "R40") (pin "2") (pinfunction "2_2") (pintype "bidirectional"))
      (node (ref "R41") (pin "2") (pinfunction "2_2") (pintype "bidirectional"))
      (node (ref "R42") (pin "2") (pinfunction "2_2") (pintype "bidirectional"))
      (node (ref "R45") (pin "1") (pinfunction "1_1") (pintype "bidirectional"))
      (node (ref "R46") (pin "2") (pinfunction "2_2") (pintype "bidirectional"))
      (node (ref "R55") (pin "2") (pinfunction "2_2") (pintype "bidirectional"))
      (node (ref "R58") (pin "1") (pinfunction "1_1") (pintype "bidirectional"))
      (node (ref "R6") (pin "2") (pinfunction "2_2") (pintype "bidirectional"))
      (node (ref "R60") (pin "2") (pinfunction "2_2") (pintype "bidirectional"))
      (node (ref "R62") (pin "2") (pinfunction "2_2") (pintype "bidirectional"))
      (node (ref "R65") (pin "1") (pinfunction "1_1") (pintype "bidirectional"))
      (node (ref "R66") (pin "2") (pinfunction "2_2") (pintype "bidirectional"))
      (node (ref "R68") (pin "2") (pinfunction "2_2") (pintype "bidirectional"))
      (node (ref "R7") (pin "2") (pinfunction "2_2") (pintype "bidirectional"))
      (node (ref "R9") (pin "1") (pinfunction "1_1") (pintype "bidirectional"))
      (node (ref "SPI-LED") (pin "GND") (pinfunction "GND_GND") (pintype "bidirectional"))
      (node (ref "ST") (pin "3") (pinfunction "3_3") (pintype "power_in"))
      (node (ref "T1") (pin "1") (pinfunction "1:GND(EMITTER)_1") (pintype "passive"))
      (node (ref "TH") (pin "3") (pinfunction "3_3") (pintype "power_in"))
      (node (ref "U$1") (pin "15") (pinfunction "15:E_15") (pintype "bidirectional"))
      (node (ref "U$1") (pin "8") (pinfunction "8:GND_8") (pintype "bidirectional"))
      (node (ref "U$10") (pin "1") (pinfunction "1:OE_1") (pintype "input"))
      (node (ref "U$10") (pin "3") (pinfunction "3:GND_3") (pintype "power_in"))
      (node (ref "U$11") (pin "#2") (pinfunction "2:CASE_GND_#2") (pintype "bidirectional"))
      (node (ref "U$14") (pin "1:GND_J3") (pinfunction "1:GND_J3_1:GND_J3") (pintype "bidirectional"))
      (node (ref "U$14") (pin "1:GND_J3R") (pinfunction "1:GND_J3_1:GND_J3R") (pintype "bidirectional"))
      (node (ref "U$14") (pin "21:GND_J3") (pinfunction "21:GND_J3_21:GND_J3") (pintype "power_in"))
      (node (ref "U$14") (pin "21:GND_J3_R") (pinfunction "21:GND_J3_21:GND_J3_R") (pintype "power_in"))
      (node (ref "U$14") (pin "22:GND_J1") (pinfunction "22:GND_J1_22:GND_J1") (pintype "power_in"))
      (node (ref "U$14") (pin "22:GND_J1L") (pinfunction "22:GND_J1_22:GND_J1L") (pintype "power_in"))
      (node (ref "U$14") (pin "22:GND_J3") (pinfunction "22:GND_J3_22:GND_J3") (pintype "power_in"))
      (node (ref "U$14") (pin "22:GND_J3_R") (pinfunction "22:GND_J3_22:GND_J3_R") (pintype "power_in"))
      (node (ref "U$3") (pin "4") (pinfunction "4:GND_4") (pintype "power_in"))
      (node (ref "U$5") (pin "4") (pinfunction "4:GND_4") (pintype "power_in"))
      (node (ref "U$9") (pin "1") (pinfunction "1:OE_1") (pintype "input"))
      (node (ref "U$9") (pin "3") (pinfunction "3:GND_3") (pintype "power_in"))
      (node (ref "U1") (pin "5") (pinfunction "5:GND_5") (pintype "bidirectional"))
      (node (ref "U6") (pin "18") (pinfunction "18:H_CSN_18") (pintype "input"))
      (node (ref "U6") (pin "2") (pinfunction "2:GND_2") (pintype "power_in"))
      (node (ref "U6") (pin "25") (pinfunction "25:GND_25") (pintype "power_in"))
      (node (ref "U6") (pin "5") (pinfunction "5:PS1_5") (pintype "input"))
      (node (ref "U6") (pin "6") (pinfunction "6:PS0/WAKE_6") (pintype "input"))
      (node (ref "U7") (pin "10") (pinfunction "D3_10") (pintype "bidirectional"))
      (node (ref "U7") (pin "14") (pinfunction "E/RD#_14") (pintype "bidirectional"))
      (node (ref "U7") (pin "15") (pinfunction "R/W#_15") (pintype "bidirectional"))
      (node (ref "U7") (pin "18") (pinfunction "CS#_18") (pintype "bidirectional"))
      (node (ref "U7") (pin "19") (pinfunction "BS2_19") (pintype "bidirectional"))
      (node (ref "U7") (pin "2") (pinfunction "VLSS_2") (pintype "bidirectional"))
      (node (ref "U7") (pin "21") (pinfunction "BS0_21") (pintype "bidirectional"))
      (node (ref "U7") (pin "23") (pinfunction "VSS_23") (pintype "bidirectional"))
      (node (ref "U7") (pin "6") (pinfunction "D7_6") (pintype "bidirectional"))
      (node (ref "U7") (pin "7") (pinfunction "D6_7") (pintype "bidirectional"))
      (node (ref "U7") (pin "8") (pinfunction "D5_8") (pintype "bidirectional"))
      (node (ref "U7") (pin "9") (pinfunction "D4_9") (pintype "bidirectional"))
    )
    (net (code "71") (name "M_SENSOR1") (class "Default")
      (node (ref "R47") (pin "1") (pinfunction "1_1") (pintype "bidirectional"))
      (node (ref "U$14") (pin "9:GPIO16") (pinfunction "9:GPIO16_9:GPIO16") (pintype "bidirectional"))
      (node (ref "U$14") (pin "9:GPIO16_L") (pinfunction "9:GPIO16_9:GPIO16_L") (pintype "bidirectional"))
      (node (ref "U$3") (pin "7") (pinfunction "7:1Y_7") (pintype "open_collector"))
    )
    (net (code "72") (name "M_SENSOR2") (class "Default")
      (node (ref "R48") (pin "1") (pinfunction "1_1") (pintype "bidirectional"))
      (node (ref "U$14") (pin "10:GPIO17") (pinfunction "10:GPIO17_10:GPIO17") (pintype "bidirectional"))
      (node (ref "U$14") (pin "10:GPIO17_L") (pinfunction "10:GPIO17_10:GPIO17_L") (pintype "bidirectional"))
      (node (ref "U$3") (pin "2") (pinfunction "2:3Y_2") (pintype "open_collector"))
    )
    (net (code "73") (name "M_SENSOR3") (class "Default")
      (node (ref "R59") (pin "1") (pinfunction "1_1") (pintype "bidirectional"))
      (node (ref "U$14") (pin "11:GPIO18") (pinfunction "11:GPIO18_11:GPIO18") (pintype "bidirectional"))
      (node (ref "U$14") (pin "11:GPIO18_L") (pinfunction "11:GPIO18_11:GPIO18_L") (pintype "bidirectional"))
      (node (ref "U$3") (pin "5") (pinfunction "5:2Y_5") (pintype "open_collector"))
    )
    (net (code "74") (name "Net-(C12-Pad2)") (class "Default")
      (node (ref "C12") (pin "2") (pinfunction "2_2") (pintype "passive"))
      (node (ref "D1") (pin "ANODE") (pinfunction "ANODE_ANODE") (pintype "bidirectional"))
      (node (ref "R25") (pin "2") (pinfunction "2_2") (pintype "bidirectional"))
      (node (ref "R31") (pin "1") (pinfunction "1_1") (pintype "bidirectional"))
    )
    (net (code "75") (name "Net-(CH4-Pad1)") (class "Default")
      (node (ref "CH4") (pin "1") (pinfunction "1_1") (pintype "bidirectional"))
      (node (ref "R54") (pin "2") (pinfunction "2_2") (pintype "bidirectional"))
    )
    (net (code "76") (name "Net-(CH5-Pad1)") (class "Default")
      (node (ref "CH5") (pin "1") (pinfunction "1_1") (pintype "bidirectional"))
      (node (ref "R61") (pin "2") (pinfunction "2_2") (pintype "bidirectional"))
    )
    (net (code "77") (name "Net-(EXT1-Pad3:DOUT)") (class "Default")
      (node (ref "EXT1") (pin "3:DOUT") (pinfunction "3:DOUT_3:DOUT") (pintype "input"))
      (node (ref "R18") (pin "2") (pinfunction "2_2") (pintype "bidirectional"))
      (node (ref "R41") (pin "1") (pinfunction "1_1") (pintype "bidirectional"))
    )
    (net (code "78") (name "Net-(EXT1-Pad4:BCLK)") (class "Default")
      (node (ref "EXT1") (pin "4:BCLK") (pinfunction "4:BCLK_4:BCLK") (pintype "input"))
      (node (ref "R30") (pin "2") (pinfunction "2_2") (pintype "bidirectional"))
    )
    (net (code "79") (name "Net-(EXT1-Pad5:LRCLK)") (class "Default")
      (node (ref "EXT1") (pin "5:LRCLK") (pinfunction "5:LRCLK_5:LRCLK") (pintype "input"))
      (node (ref "R38") (pin "2") (pinfunction "2_2") (pintype "bidirectional"))
    )
    (net (code "80") (name "Net-(IC1-BYPASS)") (class "Default")
      (node (ref "C6") (pin "2") (pinfunction "2_2") (pintype "passive"))
      (node (ref "IC1") (pin "4") (pinfunction "BYPASS_4") (pintype "bidirectional"))
    )
    (net (code "81") (name "Net-(IC2-EXTCLK)") (class "Default")
      (node (ref "C3") (pin "2") (pinfunction "2_2") (pintype "passive"))
      (node (ref "IC2") (pin "25") (pinfunction "EXTCLK_25") (pintype "bidirectional"))
      (node (ref "R1") (pin "2") (pinfunction "2_2") (pintype "bidirectional"))
      (node (ref "U$11") (pin "#3") (pinfunction "3:OUTPUT_#3") (pintype "bidirectional"))
    )
    (net (code "82") (name "Net-(IC2-LED14)") (class "Default")
      (node (ref "IC2") (pin "21") (pinfunction "LED14_21") (pintype "bidirectional"))
      (node (ref "TP2") (pin "TP") (pinfunction "TP_TP") (pintype "passive"))
    )
    (net (code "83") (name "Net-(IC2-OE)") (class "Default")
      (node (ref "IC2") (pin "23") (pinfunction "OE_23") (pintype "bidirectional"))
      (node (ref "R3") (pin "2") (pinfunction "2_2") (pintype "bidirectional"))
    )
    (net (code "84") (name "Net-(Q1-PadG)") (class "Default")
      (node (ref "Q1") (pin "G") (pinfunction "G_G") (pintype "passive"))
      (node (ref "R54") (pin "1") (pinfunction "1_1") (pintype "bidirectional"))
      (node (ref "R55") (pin "1") (pinfunction "1_1") (pintype "bidirectional"))
    )
    (net (code "85") (name "Net-(Q2-PadG)") (class "Default")
      (node (ref "Q2") (pin "G") (pinfunction "G_G") (pintype "passive"))
      (node (ref "R61") (pin "1") (pinfunction "1_1") (pintype "bidirectional"))
      (node (ref "R62") (pin "1") (pinfunction "1_1") (pintype "bidirectional"))
    )
    (net (code "86") (name "Net-(Q3-PadG)") (class "Default")
      (node (ref "Q3") (pin "G") (pinfunction "G_G") (pintype "passive"))
      (node (ref "R24") (pin "1") (pinfunction "1_1") (pintype "bidirectional"))
      (node (ref "R8") (pin "1") (pinfunction "1_1") (pintype "bidirectional"))
    )
    (net (code "87") (name "Net-(Q4-PadG)") (class "Default")
      (node (ref "Q4") (pin "G") (pinfunction "G_G") (pintype "passive"))
      (node (ref "R33") (pin "1") (pinfunction "1_1") (pintype "bidirectional"))
      (node (ref "R35") (pin "2") (pinfunction "2_2") (pintype "bidirectional"))
    )
    (net (code "88") (name "Net-(Q5-PadG)") (class "Default")
      (node (ref "Q5") (pin "G") (pinfunction "G_G") (pintype "passive"))
      (node (ref "R32") (pin "1") (pinfunction "1_1") (pintype "bidirectional"))
      (node (ref "R34") (pin "2") (pinfunction "2_2") (pintype "bidirectional"))
    )
    (net (code "89") (name "Net-(R7-Pad1)") (class "Default")
      (node (ref "R7") (pin "1") (pinfunction "1_1") (pintype "bidirectional"))
      (node (ref "RCPWR") (pin "CATHODE") (pinfunction "CATHODE_CATHODE") (pintype "passive"))
    )
    (net (code "90") (name "Net-(R63-Pad1)") (class "Default")
      (node (ref "R63") (pin "1") (pinfunction "1_1") (pintype "bidirectional"))
      (node (ref "U$14") (pin "2:GPIO43") (pinfunction "2:GPIO43/U0TXD_2:GPIO43") (pintype "bidirectional"))
      (node (ref "U$14") (pin "2:GPIO43_R") (pinfunction "2:GPIO43/U0TXD_2:GPIO43_R") (pintype "bidirectional"))
    )
    (net (code "91") (name "Net-(R64-Pad1)") (class "Default")
      (node (ref "R64") (pin "1") (pinfunction "1_1") (pintype "bidirectional"))
      (node (ref "U$14") (pin "3:GPIO44") (pinfunction "3:GPIO44/U0RXD_3:GPIO44") (pintype "bidirectional"))
      (node (ref "U$14") (pin "3:GPIO44_R") (pinfunction "3:GPIO44/U0RXD_3:GPIO44_R") (pintype "bidirectional"))
    )
    (net (code "92") (name "Net-(R78-Pad2)") (class "Default")
      (node (ref "R78") (pin "2") (pinfunction "2_2") (pintype "bidirectional"))
      (node (ref "U$14") (pin "16:GPIO10") (pinfunction "16:GPIO10_16:GPIO10") (pintype "bidirectional"))
      (node (ref "U$14") (pin "16:GPIO10_L") (pinfunction "16:GPIO10_16:GPIO10_L") (pintype "bidirectional"))
    )
    (net (code "93") (name "Net-(R79-Pad2)") (class "Default")
      (node (ref "R79") (pin "2") (pinfunction "2_2") (pintype "bidirectional"))
      (node (ref "U$14") (pin "19:GPIO13") (pinfunction "19:GPIO13_19:GPIO13") (pintype "bidirectional"))
      (node (ref "U$14") (pin "19:GPIO13_L") (pinfunction "19:GPIO13_19:GPIO13_L") (pintype "bidirectional"))
    )
    (net (code "94") (name "Net-(U$1-2:A0)") (class "Default")
      (node (ref "R75") (pin "2") (pinfunction "2_2") (pintype "bidirectional"))
      (node (ref "U$1") (pin "2") (pinfunction "2:A0_2") (pintype "bidirectional"))
      (node (ref "U$5") (pin "7") (pinfunction "7:1Y_7") (pintype "open_collector"))
    )
    (net (code "95") (name "Net-(U$1-5:A1)") (class "Default")
      (node (ref "R74") (pin "2") (pinfunction "2_2") (pintype "bidirectional"))
      (node (ref "U$1") (pin "5") (pinfunction "5:A1_5") (pintype "bidirectional"))
      (node (ref "U$5") (pin "5") (pinfunction "5:2Y_5") (pintype "open_collector"))
    )
    (net (code "96") (name "Net-(U$1-10:B2)") (class "Default")
      (node (ref "R45") (pin "2") (pinfunction "2_2") (pintype "bidirectional"))
      (node (ref "U$1") (pin "10") (pinfunction "10:B2_10") (pintype "bidirectional"))
    )
    (net (code "97") (name "Net-(U$1-11:A2)") (class "Default")
      (node (ref "R17") (pin "2") (pinfunction "2_2") (pintype "bidirectional"))
      (node (ref "U$1") (pin "11") (pinfunction "11:A2_11") (pintype "bidirectional"))
    )
    (net (code "98") (name "Net-(U$1-13:B3)") (class "Default")
      (node (ref "R9") (pin "2") (pinfunction "2_2") (pintype "bidirectional"))
      (node (ref "U$1") (pin "13") (pinfunction "13:B3_13") (pintype "bidirectional"))
    )
    (net (code "99") (name "Net-(U$1-14:A3)") (class "Default")
      (node (ref "R65") (pin "2") (pinfunction "2_2") (pintype "bidirectional"))
      (node (ref "U$1") (pin "14") (pinfunction "14:A3_14") (pintype "bidirectional"))
    )
    (net (code "100") (name "Net-(U$5-6:3A)") (class "Default")
      (node (ref "R73") (pin "2") (pinfunction "2_2") (pintype "bidirectional"))
      (node (ref "U$5") (pin "6") (pinfunction "6:3A_6") (pintype "input"))
    )
    (net (code "101") (name "Net-(U$9-4:Y)") (class "Default")
      (node (ref "LED1") (pin "SDI") (pinfunction "SDI_SDI") (pintype "bidirectional"))
      (node (ref "U$9") (pin "4") (pinfunction "4:Y_4") (pintype "output"))
    )
    (net (code "102") (name "Net-(U$10-4:Y)") (class "Default")
      (node (ref "LED1") (pin "CKI") (pinfunction "CKI_CKI") (pintype "bidirectional"))
      (node (ref "U$10") (pin "4") (pinfunction "4:Y_4") (pintype "output"))
    )
    (net (code "103") (name "Net-(U$14-1:3V3-Pad1:3V3_L)") (class "Default")
      (node (ref "U$14") (pin "1:3V3") (pinfunction "1:3V3_1:3V3") (pintype "power_in"))
      (node (ref "U$14") (pin "1:3V3_L") (pinfunction "1:3V3_1:3V3_L") (pintype "power_in"))
    )
    (net (code "104") (name "Net-(U$14-2:3V3-Pad2:3V3_L)") (class "Default")
      (node (ref "U$14") (pin "2:3V3") (pinfunction "2:3V3_2:3V3") (pintype "power_in"))
      (node (ref "U$14") (pin "2:3V3_L") (pinfunction "2:3V3_2:3V3_L") (pintype "power_in"))
    )
    (net (code "105") (name "Net-(U$14-3:RST(CHIP_PU)-Pad3:RST)") (class "Default")
      (node (ref "U$14") (pin "3:RST") (pinfunction "3:RST(CHIP_PU)_3:RST") (pintype "input"))
      (node (ref "U$14") (pin "3:RST_L") (pinfunction "3:RST(CHIP_PU)_3:RST_L") (pintype "input"))
    )
    (net (code "106") (name "Net-(U$14-4:GPIO1-Pad4:GPIO1_R)") (class "Default")
      (node (ref "U$14") (pin "4:GPIO1") (pinfunction "4:GPIO1_4:GPIO1") (pintype "bidirectional"))
      (node (ref "U$14") (pin "4:GPIO1_R") (pinfunction "4:GPIO1_4:GPIO1_R") (pintype "bidirectional"))
    )
    (net (code "107") (name "Net-(U$14-5:GPOP2-Pad5:GPIO2)") (class "Default")
      (node (ref "U$14") (pin "5:GPIO2") (pinfunction "5:GPOP2_5:GPIO2") (pintype "bidirectional"))
      (node (ref "U$14") (pin "5:GPIO2_R") (pinfunction "5:GPOP2_5:GPIO2_R") (pintype "bidirectional"))
    )
    (net (code "108") (name "Net-(U$14-6:GPIO42-Pad6:GPIO42_R)") (class "Default")
      (node (ref "U$14") (pin "6:GPIO42") (pinfunction "6:GPIO42_6:GPIO42") (pintype "bidirectional"))
      (node (ref "U$14") (pin "6:GPIO42_R") (pinfunction "6:GPIO42_6:GPIO42_R") (pintype "bidirectional"))
    )
    (net (code "109") (name "Net-(U$14-7:GPIO41-Pad7:GPIO41_R)") (class "Default")
      (node (ref "U$14") (pin "7:GPIO41") (pinfunction "7:GPIO41_7:GPIO41") (pintype "bidirectional"))
      (node (ref "U$14") (pin "7:GPIO41_R") (pinfunction "7:GPIO41_7:GPIO41_R") (pintype "bidirectional"))
    )
    (net (code "110") (name "Net-(U$14-8:GPIO40-Pad8:GPIO40_R)") (class "Default")
      (node (ref "U$14") (pin "8:GPIO40") (pinfunction "8:GPIO40_8:GPIO40") (pintype "bidirectional"))
      (node (ref "U$14") (pin "8:GPIO40_R") (pinfunction "8:GPIO40_8:GPIO40_R") (pintype "bidirectional"))
    )
    (net (code "111") (name "Net-(U$14-9:GPIO39-Pad9:GPIO39_R)") (class "Default")
      (node (ref "U$14") (pin "9:GPIO39") (pinfunction "9:GPIO39_9:GPIO39") (pintype "bidirectional"))
      (node (ref "U$14") (pin "9:GPIO39_R") (pinfunction "9:GPIO39_9:GPIO39_R") (pintype "bidirectional"))
    )
    (net (code "112") (name "Net-(U$14-10:GPIO38-Pad10:GPIO38_R)") (class "Default")
      (node (ref "U$14") (pin "10:GPIO38") (pinfunction "10:GPIO38_10:GPIO38") (pintype "bidirectional"))
      (node (ref "U$14") (pin "10:GPIO38_R") (pinfunction "10:GPIO38_10:GPIO38_R") (pintype "bidirectional"))
    )
    (net (code "113") (name "Net-(U$14-11:GPIO37-Pad11:GPIO37_R)") (class "Default")
      (node (ref "U$14") (pin "11:GPIO37") (pinfunction "11:GPIO37_11:GPIO37") (pintype "bidirectional"))
      (node (ref "U$14") (pin "11:GPIO37_R") (pinfunction "11:GPIO37_11:GPIO37_R") (pintype "bidirectional"))
    )
    (net (code "114") (name "Net-(U$14-12:GPIO36-Pad12:GPIO36_R)") (class "Default")
      (node (ref "U$14") (pin "12:GPIO36") (pinfunction "12:GPIO36_12:GPIO36") (pintype "bidirectional"))
      (node (ref "U$14") (pin "12:GPIO36_R") (pinfunction "12:GPIO36_12:GPIO36_R") (pintype "bidirectional"))
    )
    (net (code "115") (name "Net-(U$14-13:GPIO3{slash}JTAG-Pad13:GPIO3)") (class "Default")
      (node (ref "U$14") (pin "13:GPIO3") (pinfunction "13:GPIO3/JTAG_13:GPIO3") (pintype "input"))
      (node (ref "U$14") (pin "13:GPIO3_L") (pinfunction "13:GPIO3/JTAG_13:GPIO3_L") (pintype "input"))
    )
    (net (code "116") (name "Net-(U$14-13:GPIO35-Pad13:GPIO35_R)") (class "Default")
      (node (ref "U$14") (pin "13:GPIO35") (pinfunction "13:GPIO35_13:GPIO35") (pintype "bidirectional"))
      (node (ref "U$14") (pin "13:GPIO35_R") (pinfunction "13:GPIO35_13:GPIO35_R") (pintype "bidirectional"))
    )
    (net (code "117") (name "Net-(U$14-14:GPIO0{slash}BOOT-Pad14:GPIO0)") (class "Default")
      (node (ref "U$14") (pin "14:GPIO0") (pinfunction "14:GPIO0/BOOT_14:GPIO0") (pintype "input"))
      (node (ref "U$14") (pin "14:GPIO0_R") (pinfunction "14:GPIO0/BOOT_14:GPIO0_R") (pintype "input"))
    )
    (net (code "118") (name "Net-(U$14-14:GPIO46{slash}LOG-Pad14:GPIO46)") (class "Default")
      (node (ref "U$14") (pin "14:GPIO46") (pinfunction "14:GPIO46/LOG_14:GPIO46") (pintype "input"))
      (node (ref "U$14") (pin "14:GPIO46_L") (pinfunction "14:GPIO46/LOG_14:GPIO46_L") (pintype "input"))
    )
    (net (code "119") (name "Net-(U$14-16:GPIO48-Pad16:GPIO48_R)") (class "Default")
      (node (ref "U$14") (pin "16:GPIO48") (pinfunction "16:GPIO48_16:GPIO48") (pintype "bidirectional"))
      (node (ref "U$14") (pin "16:GPIO48_R") (pinfunction "16:GPIO48_16:GPIO48_R") (pintype "bidirectional"))
    )
    (net (code "120") (name "Net-(U$14-18:GPIO21-Pad18:GPIO21_R)") (class "Default")
      (node (ref "U$14") (pin "18:GPIO21") (pinfunction "18:GPIO21_18:GPIO21") (pintype "bidirectional"))
      (node (ref "U$14") (pin "18:GPIO21_R") (pinfunction "18:GPIO21_18:GPIO21_R") (pintype "bidirectional"))
    )
    (net (code "121") (name "Net-(U$14-19:GPIO20{slash}USBD+-Pad19:GPIO20)") (class "Default")
      (node (ref "U$14") (pin "19:GPIO20") (pinfunction "19:GPIO20/USBD+_19:GPIO20") (pintype "bidirectional"))
      (node (ref "U$14") (pin "19:GPIO20_R") (pinfunction "19:GPIO20/USBD+_19:GPIO20_R") (pintype "bidirectional"))
    )
    (net (code "122") (name "Net-(U$14-20:GPIO14-Pad20:GPIO14_L)") (class "Default")
      (node (ref "U$14") (pin "20:GPIO14") (pinfunction "20:GPIO14_20:GPIO14") (pintype "bidirectional"))
      (node (ref "U$14") (pin "20:GPIO14_L") (pinfunction "20:GPIO14_20:GPIO14_L") (pintype "bidirectional"))
    )
    (net (code "123") (name "Net-(U$14-20:GPIO19{slash}USBD--Pad20:GPIO19)") (class "Default")
      (node (ref "U$14") (pin "20:GPIO19") (pinfunction "20:GPIO19/USBD-_20:GPIO19") (pintype "bidirectional"))
      (node (ref "U$14") (pin "20:GPIO19_R") (pinfunction "20:GPIO19/USBD-_20:GPIO19_R") (pintype "bidirectional"))
    )
    (net (code "124") (name "Net-(U1-1:AN1)") (class "Default")
      (node (ref "R16") (pin "1") (pinfunction "1_1") (pintype "bidirectional"))
      (node (ref "R29") (pin "1") (pinfunction "1_1") (pintype "bidirectional"))
      (node (ref "U1") (pin "1") (pinfunction "1:AN1_1") (pintype "bidirectional"))
    )
    (net (code "125") (name "Net-(U1-2:CA1)") (class "Default")
      (node (ref "Q5") (pin "D") (pinfunction "D_D") (pintype "passive"))
      (node (ref "R29") (pin "2") (pinfunction "2_2") (pintype "bidirectional"))
      (node (ref "U1") (pin "2") (pinfunction "2:CA1_2") (pintype "bidirectional"))
    )
    (net (code "126") (name "Net-(U1-3:CA2)") (class "Default")
      (node (ref "Q4") (pin "D") (pinfunction "D_D") (pintype "passive"))
      (node (ref "R27") (pin "1") (pinfunction "1_1") (pintype "bidirectional"))
      (node (ref "U1") (pin "3") (pinfunction "3:CA2_3") (pintype "bidirectional"))
    )
    (net (code "127") (name "Net-(U1-4:AN2)") (class "Default")
      (node (ref "R15") (pin "1") (pinfunction "1_1") (pintype "bidirectional"))
      (node (ref "R27") (pin "2") (pinfunction "2_2") (pintype "bidirectional"))
      (node (ref "U1") (pin "4") (pinfunction "4:AN2_4") (pintype "bidirectional"))
    )
    (net (code "128") (name "Net-(U2-A)") (class "Default")
      (node (ref "R26") (pin "1") (pinfunction "1_1") (pintype "bidirectional"))
      (node (ref "U2") (pin "1") (pinfunction "A_1") (pintype "passive"))
    )
    (net (code "129") (name "Net-(U2-C)") (class "Default")
      (node (ref "Q3") (pin "D") (pinfunction "D_D") (pintype "passive"))
      (node (ref "R53") (pin "2") (pinfunction "2_2") (pintype "bidirectional"))
      (node (ref "U2") (pin "2") (pinfunction "C_2") (pintype "passive"))
    )
    (net (code "130") (name "Net-(U3-A)") (class "Default")
      (node (ref "R56") (pin "1") (pinfunction "1_1") (pintype "bidirectional"))
      (node (ref "U3") (pin "1") (pinfunction "A_1") (pintype "passive"))
    )
    (net (code "131") (name "Net-(U3-C)") (class "Default")
      (node (ref "Q1") (pin "D") (pinfunction "D_D") (pintype "passive"))
      (node (ref "U3") (pin "2") (pinfunction "C_2") (pintype "passive"))
    )
    (net (code "132") (name "Net-(U4-A)") (class "Default")
      (node (ref "R67") (pin "1") (pinfunction "1_1") (pintype "bidirectional"))
      (node (ref "U4") (pin "1") (pinfunction "A_1") (pintype "passive"))
    )
    (net (code "133") (name "Net-(U4-C)") (class "Default")
      (node (ref "Q2") (pin "D") (pinfunction "D_D") (pintype "passive"))
      (node (ref "U4") (pin "2") (pinfunction "C_2") (pintype "passive"))
    )
    (net (code "134") (name "Net-(U6-4:BOOTN)") (class "Default")
      (node (ref "BOOTSEL") (pin "TP") (pinfunction "TP_TP") (pintype "passive"))
      (node (ref "R70") (pin "1") (pinfunction "1_1") (pintype "bidirectional"))
      (node (ref "U6") (pin "4") (pinfunction "4:BOOTN_4") (pintype "input"))
    )
    (net (code "135") (name "Net-(U6-9:CAP)") (class "Default")
      (node (ref "C21") (pin "2") (pinfunction "2_2") (pintype "passive"))
      (node (ref "U6") (pin "9") (pinfunction "9:CAP_9") (pintype "bidirectional"))
    )
    (net (code "136") (name "Net-(U6-10:CLKSEL0)") (class "Default")
      (node (ref "R80") (pin "1") (pinfunction "1_1") (pintype "bidirectional"))
      (node (ref "U6") (pin "10") (pinfunction "10:CLKSEL0_10") (pintype "input"))
    )
    (net (code "137") (name "Net-(U6-11:NRST)") (class "Default")
      (node (ref "R69") (pin "1") (pinfunction "1_1") (pintype "bidirectional"))
      (node (ref "R71") (pin "2") (pinfunction "2_2") (pintype "bidirectional"))
      (node (ref "U6") (pin "11") (pinfunction "11:NRST_11") (pintype "input"))
    )
    (net (code "138") (name "Net-(U6-14:H_INTN)") (class "Default")
      (node (ref "INIT") (pin "TP") (pinfunction "TP_TP") (pintype "passive"))
      (node (ref "U6") (pin "14") (pinfunction "14:H_INTN_14") (pintype "output"))
    )
    (net (code "139") (name "Net-(U6-17:SA0{slash}H_MOSI)") (class "Default")
      (node (ref "R58") (pin "2") (pinfunction "2_2") (pintype "bidirectional"))
      (node (ref "R72") (pin "1") (pinfunction "1_1") (pintype "bidirectional"))
      (node (ref "U6") (pin "17") (pinfunction "17:SA0/H_MOSI_17") (pintype "input"))
    )
    (net (code "140") (name "Net-(U6-26:XOUT32{slash}CLKSEL1)") (class "Default")
      (node (ref "C25") (pin "1") (pinfunction "1_1") (pintype "passive"))
      (node (ref "U6") (pin "26") (pinfunction "26:XOUT32/CLKSEL1_26") (pintype "output"))
      (node (ref "X1") (pin "2") (pinfunction "P$2_2") (pintype "bidirectional"))
    )
    (net (code "141") (name "Net-(U6-27:XIN32)") (class "Default")
      (node (ref "C24") (pin "1") (pinfunction "1_1") (pintype "passive"))
      (node (ref "U6") (pin "27") (pinfunction "27:XIN32_27") (pintype "input"))
      (node (ref "X1") (pin "1") (pinfunction "P$1_1") (pintype "bidirectional"))
    )
    (net (code "142") (name "Net-(U7-BS1)") (class "Default")
      (node (ref "R19") (pin "2") (pinfunction "2_2") (pintype "bidirectional"))
      (node (ref "U7") (pin "20") (pinfunction "BS1_20") (pintype "bidirectional"))
    )
    (net (code "143") (name "Net-(U7-C1N)") (class "Default")
      (node (ref "C19") (pin "1") (pinfunction "1_1") (pintype "passive"))
      (node (ref "U7") (pin "26") (pinfunction "C1N_26") (pintype "bidirectional"))
    )
    (net (code "144") (name "Net-(U7-C1P)") (class "Default")
      (node (ref "C19") (pin "2") (pinfunction "2_2") (pintype "passive"))
      (node (ref "U7") (pin "27") (pinfunction "C1P_27") (pintype "bidirectional"))
    )
    (net (code "145") (name "Net-(U7-C2N)") (class "Default")
      (node (ref "C22") (pin "1") (pinfunction "1_1") (pintype "passive"))
      (node (ref "U7") (pin "28") (pinfunction "C2N_28") (pintype "bidirectional"))
    )
    (net (code "146") (name "Net-(U7-C2P)") (class "Default")
      (node (ref "C22") (pin "2") (pinfunction "2_2") (pintype "passive"))
      (node (ref "U7") (pin "29") (pinfunction "C2P_29") (pintype "bidirectional"))
    )
    (net (code "147") (name "Net-(U7-D{slash}C#)") (class "Default")
      (node (ref "R36") (pin "2") (pinfunction "2_2") (pintype "bidirectional"))
      (node (ref "R37") (pin "1") (pinfunction "1_1") (pintype "bidirectional"))
      (node (ref "U7") (pin "16") (pinfunction "D/C#_16") (pintype "bidirectional"))
    )
    (net (code "148") (name "Net-(U7-IREF)") (class "Default")
      (node (ref "R13") (pin "1") (pinfunction "1_1") (pintype "bidirectional"))
      (node (ref "U7") (pin "5") (pinfunction "IREF_5") (pintype "bidirectional"))
    )
    (net (code "149") (name "Net-(U7-VCC)") (class "Default")
      (node (ref "C13") (pin "2") (pinfunction "2_2") (pintype "passive"))
      (node (ref "U7") (pin "3") (pinfunction "VCC_3") (pintype "bidirectional"))
    )
    (net (code "150") (name "Net-(U7-VCOMH)") (class "Default")
      (node (ref "C16") (pin "2") (pinfunction "2_2") (pintype "passive"))
      (node (ref "U7") (pin "4") (pinfunction "VCOMH_4") (pintype "bidirectional"))
    )
    (net (code "151") (name "VSPI") (class "Default")
      (node (ref "R76") (pin "1") (pinfunction "1_1") (pintype "bidirectional"))
      (node (ref "R77") (pin "1") (pinfunction "1_1") (pintype "bidirectional"))
      (node (ref "R78") (pin "1") (pinfunction "1_1") (pintype "bidirectional"))
      (node (ref "R79") (pin "1") (pinfunction "1_1") (pintype "bidirectional"))
      (node (ref "U$14") (pin "15:GPIO45") (pinfunction "15:GPIO45/VSPI_15:GPIO45") (pintype "power_in"))
      (node (ref "U$14") (pin "15:GPIO45_R") (pinfunction "15:GPIO45/VSPI_15:GPIO45_R") (pintype "power_in"))
    )
    (net (code "152") (name "unconnected-(GPIO40-CE1-Pad26)") (class "Default")
      (node (ref "GPIO40") (pin "26") (pinfunction "CE1_26") (pintype "bidirectional"))
    )
    (net (code "153") (name "unconnected-(GPIO40-ID_SC-Pad28)") (class "Default")
      (node (ref "GPIO40") (pin "28") (pinfunction "ID_SC_28") (pintype "bidirectional"))
    )
    (net (code "154") (name "unconnected-(GPIO40-ID_SD-Pad27)") (class "Default")
      (node (ref "GPIO40") (pin "27") (pinfunction "ID_SD_27") (pintype "bidirectional"))
    )
    (net (code "155") (name "unconnected-(IC2-LED2-Pad8)") (class "Default")
      (node (ref "IC2") (pin "8") (pinfunction "LED2_8") (pintype "bidirectional"))
    )
    (net (code "156") (name "unconnected-(IC2-LED3-Pad9)") (class "Default")
      (node (ref "IC2") (pin "9") (pinfunction "LED3_9") (pintype "bidirectional"))
    )
    (net (code "157") (name "unconnected-(IC2-LED4-Pad10)") (class "Default")
      (node (ref "IC2") (pin "10") (pinfunction "LED4_10") (pintype "bidirectional"))
    )
    (net (code "158") (name "unconnected-(IC2-LED5-Pad11)") (class "Default")
      (node (ref "IC2") (pin "11") (pinfunction "LED5_11") (pintype "bidirectional"))
    )
    (net (code "159") (name "unconnected-(IC2-LED6-Pad12)") (class "Default")
      (node (ref "IC2") (pin "12") (pinfunction "LED6_12") (pintype "bidirectional"))
    )
    (net (code "160") (name "unconnected-(IC2-LED7-Pad13)") (class "Default")
      (node (ref "IC2") (pin "13") (pinfunction "LED7_13") (pintype "bidirectional"))
    )
    (net (code "161") (name "unconnected-(IC2-LED8-Pad15)") (class "Default")
      (node (ref "IC2") (pin "15") (pinfunction "LED8_15") (pintype "bidirectional"))
    )
    (net (code "162") (name "unconnected-(IC2-LED9-Pad16)") (class "Default")
      (node (ref "IC2") (pin "16") (pinfunction "LED9_16") (pintype "bidirectional"))
    )
    (net (code "163") (name "unconnected-(IC2-LED10-Pad17)") (class "Default")
      (node (ref "IC2") (pin "17") (pinfunction "LED10_17") (pintype "bidirectional"))
    )
    (net (code "164") (name "unconnected-(IC2-LED11-Pad18)") (class "Default")
      (node (ref "IC2") (pin "18") (pinfunction "LED11_18") (pintype "bidirectional"))
    )
    (net (code "165") (name "unconnected-(IC2-LED12-Pad19)") (class "Default")
      (node (ref "IC2") (pin "19") (pinfunction "LED12_19") (pintype "bidirectional"))
    )
    (net (code "166") (name "unconnected-(IC2-LED13-Pad20)") (class "Default")
      (node (ref "IC2") (pin "20") (pinfunction "LED13_20") (pintype "bidirectional"))
    )
    (net (code "167") (name "unconnected-(IC2-LED15-Pad22)") (class "Default")
      (node (ref "IC2") (pin "22") (pinfunction "LED15_22") (pintype "bidirectional"))
    )
    (net (code "168") (name "unconnected-(U$1-9:Y2-Pad9)") (class "Default")
      (node (ref "U$1") (pin "9") (pinfunction "9:Y2_9") (pintype "bidirectional"))
    )
    (net (code "169") (name "unconnected-(U$1-12:Y3-Pad12)") (class "Default")
      (node (ref "U$1") (pin "12") (pinfunction "12:Y3_12") (pintype "bidirectional"))
    )
    (net (code "170") (name "unconnected-(U$5-2:3Y-Pad2)") (class "Default")
      (node (ref "U$5") (pin "2") (pinfunction "2:3Y_2") (pintype "open_collector"))
    )
    (net (code "171") (name "unconnected-(U6-1:RESV_NC-Pad1)") (class "Default")
      (node (ref "U6") (pin "1") (pinfunction "1:RESV_NC_1") (pintype "no_connect"))
    )
    (net (code "172") (name "unconnected-(U6-7:RESV_NC-Pad7)") (class "Default")
      (node (ref "U6") (pin "7") (pinfunction "7:RESV_NC_7") (pintype "no_connect"))
    )
    (net (code "173") (name "unconnected-(U6-8:RESV_NC-Pad8)") (class "Default")
      (node (ref "U6") (pin "8") (pinfunction "8:RESV_NC_8") (pintype "no_connect"))
    )
    (net (code "174") (name "unconnected-(U6-12:RESV_NC-Pad12)") (class "Default")
      (node (ref "U6") (pin "12") (pinfunction "12:RESV_NC_12") (pintype "no_connect"))
    )
    (net (code "175") (name "unconnected-(U6-13:RESV_NC-Pad13)") (class "Default")
      (node (ref "U6") (pin "13") (pinfunction "13:RESV_NC_13") (pintype "no_connect"))
    )
    (net (code "176") (name "unconnected-(U6-15:ENV_SCL-Pad15)") (class "Default")
      (node (ref "U6") (pin "15") (pinfunction "15:ENV_SCL_15") (pintype "bidirectional"))
    )
    (net (code "177") (name "unconnected-(U6-16:ENV_SDA-Pad16)") (class "Default")
      (node (ref "U6") (pin "16") (pinfunction "16:ENV_SDA_16") (pintype "bidirectional"))
    )
    (net (code "178") (name "unconnected-(U6-21:RESV_NC-Pad21)") (class "Default")
      (node (ref "U6") (pin "21") (pinfunction "21:RESV_NC_21") (pintype "no_connect"))
    )
    (net (code "179") (name "unconnected-(U6-22:RESV_NC-Pad22)") (class "Default")
      (node (ref "U6") (pin "22") (pinfunction "22:RESV_NC_22") (pintype "no_connect"))
    )
    (net (code "180") (name "unconnected-(U6-23:RESV_NC-Pad23)") (class "Default")
      (node (ref "U6") (pin "23") (pinfunction "23:RESV_NC_23") (pintype "no_connect"))
    )
    (net (code "181") (name "unconnected-(U6-24:RESV_NC-Pad24)") (class "Default")
      (node (ref "U6") (pin "24") (pinfunction "24:RESV_NC_24") (pintype "no_connect"))
    )
    (net (code "182") (name "unconnected-(U7-NC-Pad1)") (class "Default")
      (node (ref "U7") (pin "1") (pinfunction "NC_1") (pintype "bidirectional"))
    )
    (net (code "183") (name "unconnected-(U7-NC-Pad24)") (class "Default")
      (node (ref "U7") (pin "24") (pinfunction "NC_24") (pintype "bidirectional"))
    )
    (net (code "184") (name "unconnected-(U7-NC-Pad30)") (class "Default")
      (node (ref "U7") (pin "30") (pinfunction "NC_30") (pintype "bidirectional"))
    )
  )
)
